# Maduino_Zero_4G_LTE_CAT4_SIM7600X-H_v1_3.net
KiCad netlist of a schematic drawn in EAGLE
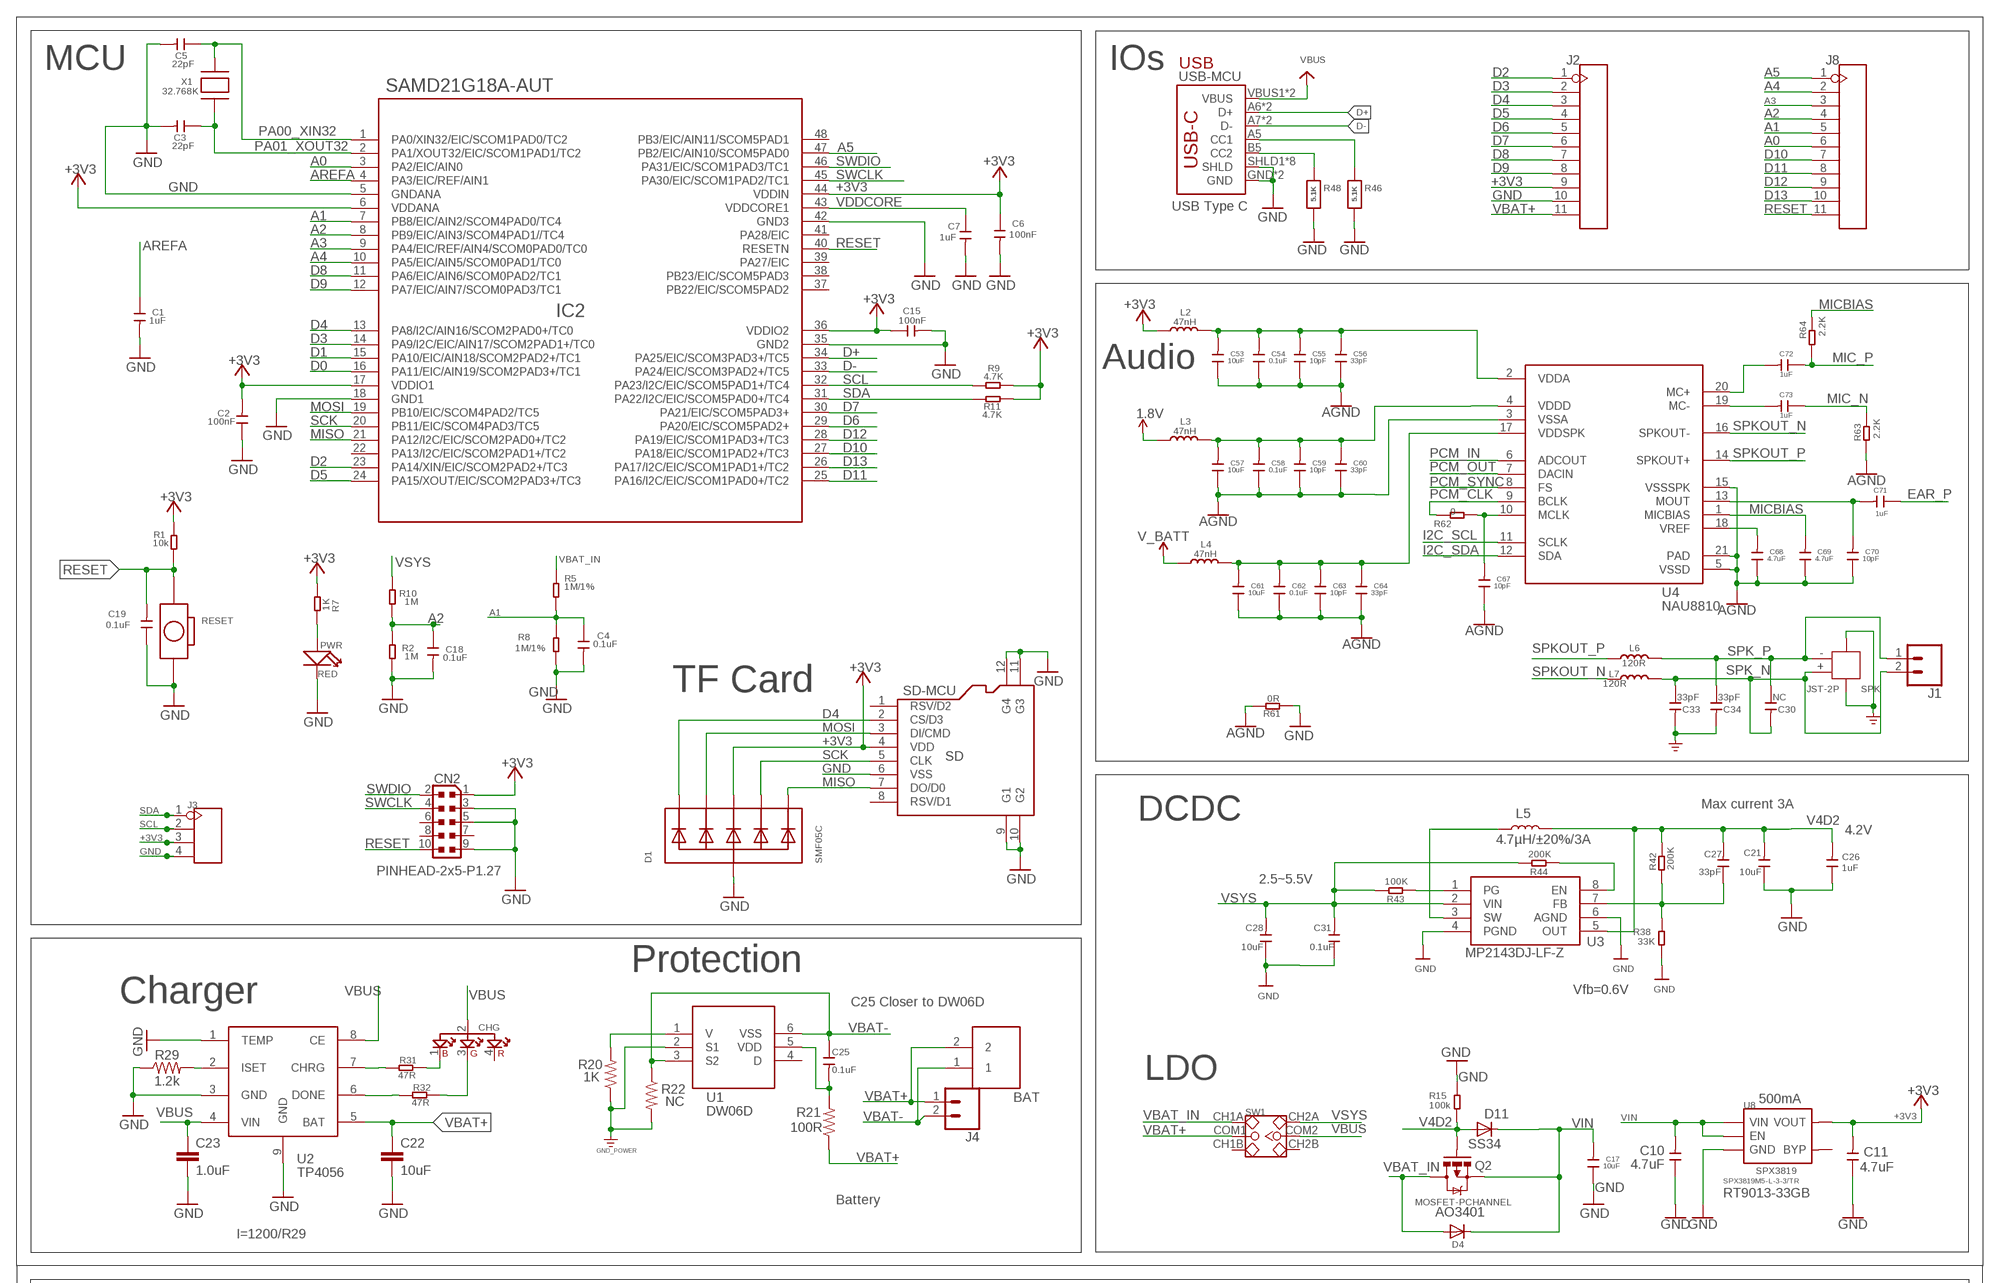
[diagram p0: schematic, sheet 1, part 1 of 2]
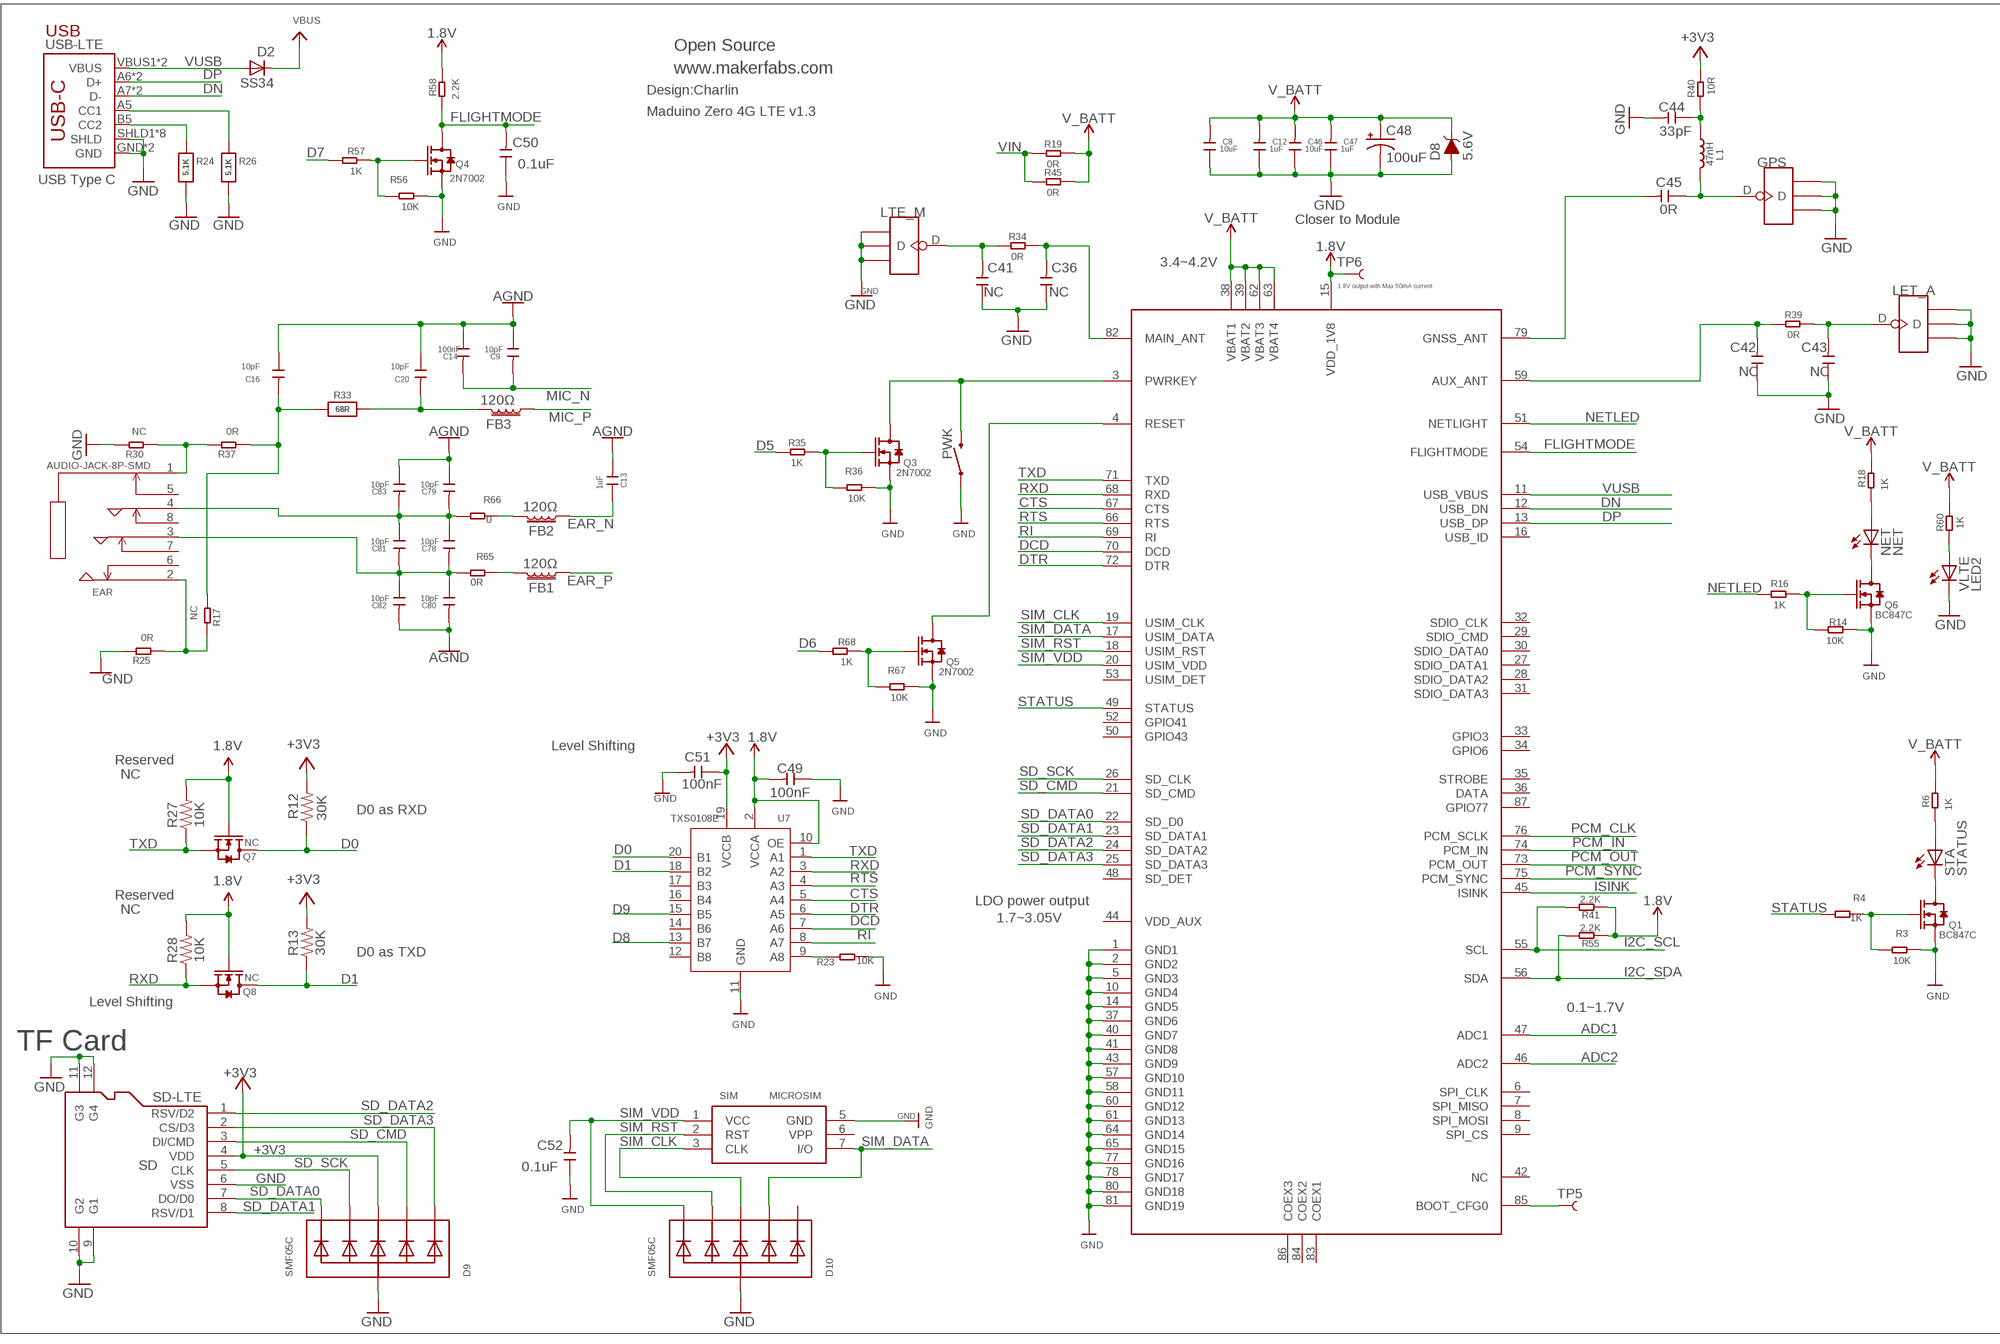
[diagram p1: schematic, sheet 1, part 2 of 2]

(export (version "E")
  (design (tool "Eeschema 10.0.6"))
  (components
    (comp (ref "BAT")
      (value "PH2.0-2P-90-DIP")
      (footprint "eagle-import:PH2.0-2P-90-DIP")
      (libsource (lib "eagle-import") (part "PH2.0-2P-90-DIP"))
    )
    (comp (ref "C1")
      (value "1uF")
      (footprint "eagle-import:0603")
      (libsource (lib "eagle-import") (part "C-0603"))
    )
    (comp (ref "C2")
      (value "100nF")
      (footprint "eagle-import:0603")
      (libsource (lib "eagle-import") (part "C-0603"))
    )
    (comp (ref "C3")
      (value "22pF")
      (footprint "eagle-import:0603")
      (libsource (lib "eagle-import") (part "C-0603"))
    )
    (comp (ref "C4")
      (value "0.1uF")
      (footprint "eagle-import:0603")
      (libsource (lib "eagle-import") (part "C-0603"))
    )
    (comp (ref "C5")
      (value "22pF")
      (footprint "eagle-import:0603")
      (libsource (lib "eagle-import") (part "C-0603"))
    )
    (comp (ref "C6")
      (value "100nF")
      (footprint "eagle-import:0603")
      (libsource (lib "eagle-import") (part "C-0603"))
    )
    (comp (ref "C7")
      (value "1uF")
      (footprint "eagle-import:0603")
      (libsource (lib "eagle-import") (part "C-0603"))
    )
    (comp (ref "C8")
      (value "10uF")
      (footprint "eagle-import:0603")
      (libsource (lib "eagle-import") (part "C-0603"))
    )
    (comp (ref "C9")
      (value "10pF")
      (footprint "eagle-import:0603")
      (libsource (lib "eagle-import") (part "C-0603"))
    )
    (comp (ref "C10")
      (value "4.7uF")
      (footprint "eagle-import:0603")
      (libsource (lib "eagle-import") (part "C-0603"))
    )
    (comp (ref "C11")
      (value "4.7uF")
      (footprint "eagle-import:0603")
      (libsource (lib "eagle-import") (part "C-0603"))
    )
    (comp (ref "C12")
      (value "1uF")
      (footprint "eagle-import:0603")
      (libsource (lib "eagle-import") (part "C-0603"))
    )
    (comp (ref "C13")
      (value "1uF")
      (footprint "eagle-import:0603")
      (libsource (lib "eagle-import") (part "C-0603"))
    )
    (comp (ref "C14")
      (value "100nF")
      (footprint "eagle-import:0603")
      (libsource (lib "eagle-import") (part "C-0603"))
    )
    (comp (ref "C15")
      (value "100nF")
      (footprint "eagle-import:0603")
      (libsource (lib "eagle-import") (part "C-0603"))
    )
    (comp (ref "C16")
      (value "10pF")
      (footprint "eagle-import:0603")
      (libsource (lib "eagle-import") (part "C-0603"))
    )
    (comp (ref "C17")
      (value "10uF")
      (footprint "eagle-import:0603")
      (libsource (lib "eagle-import") (part "C-0603"))
    )
    (comp (ref "C18")
      (value "0.1uF")
      (footprint "eagle-import:0603")
      (libsource (lib "eagle-import") (part "C-0603"))
    )
    (comp (ref "C19")
      (value "0.1uF")
      (footprint "eagle-import:0603")
      (libsource (lib "eagle-import") (part "C-0603"))
    )
    (comp (ref "C20")
      (value "10pF")
      (footprint "eagle-import:0603")
      (libsource (lib "eagle-import") (part "C-0603"))
    )
    (comp (ref "C21")
      (value "10uF")
      (footprint "eagle-import:0603")
      (libsource (lib "eagle-import") (part "C-0603"))
    )
    (comp (ref "C22")
      (value "10uF")
      (footprint "eagle-import:0603")
      (fields (field (name "PROD_ID") "CAP-00868"))
      (libsource (lib "eagle-import") (part "1.0UF-0603-16V-10%"))
    )
    (comp (ref "C23")
      (value "1.0uF")
      (footprint "eagle-import:0603")
      (libsource (lib "eagle-import") (part "1.0UF-0603-16V-10%"))
    )
    (comp (ref "C25")
      (value "0.1uF")
      (footprint "eagle-import:0603")
      (libsource (lib "eagle-import") (part "C-0603"))
    )
    (comp (ref "C26")
      (value "1uF")
      (footprint "eagle-import:0603")
      (libsource (lib "eagle-import") (part "C-0603"))
    )
    (comp (ref "C27")
      (value "33pF")
      (footprint "eagle-import:0603")
      (libsource (lib "eagle-import") (part "C-0603"))
    )
    (comp (ref "C28")
      (value "10uF")
      (footprint "eagle-import:0603")
      (libsource (lib "eagle-import") (part "C-0603"))
    )
    (comp (ref "C30")
      (value "NC")
      (footprint "eagle-import:C0603")
      (libsource (lib "eagle-import") (part "CAP-0603"))
    )
    (comp (ref "C31")
      (value "0.1uF")
      (footprint "eagle-import:0603")
      (libsource (lib "eagle-import") (part "C-0603"))
    )
    (comp (ref "C33")
      (value "33pF")
      (footprint "eagle-import:C0603")
      (libsource (lib "eagle-import") (part "CAP-0603"))
    )
    (comp (ref "C34")
      (value "33pF")
      (footprint "eagle-import:C0603")
      (libsource (lib "eagle-import") (part "CAP-0603"))
    )
    (comp (ref "C36")
      (value "NC")
      (footprint "eagle-import:0603")
      (libsource (lib "eagle-import") (part "C-0603"))
    )
    (comp (ref "C41")
      (value "NC")
      (footprint "eagle-import:0603")
      (libsource (lib "eagle-import") (part "C-0603"))
    )
    (comp (ref "C42")
      (value "NC")
      (footprint "eagle-import:0603")
      (libsource (lib "eagle-import") (part "C-0603"))
    )
    (comp (ref "C43")
      (value "NC")
      (footprint "eagle-import:0603")
      (libsource (lib "eagle-import") (part "C-0603"))
    )
    (comp (ref "C44")
      (value "33pF")
      (footprint "eagle-import:0603")
      (libsource (lib "eagle-import") (part "C-0603"))
    )
    (comp (ref "C45")
      (value "0R")
      (footprint "eagle-import:0603")
      (libsource (lib "eagle-import") (part "C-0603"))
    )
    (comp (ref "C46")
      (value "10uF")
      (footprint "eagle-import:0603")
      (libsource (lib "eagle-import") (part "C-0603"))
    )
    (comp (ref "C47")
      (value "1uF")
      (footprint "eagle-import:0603")
      (libsource (lib "eagle-import") (part "C-0603"))
    )
    (comp (ref "C48")
      (value "100uF")
      (footprint "eagle-import:EIA3528")
      (libsource (lib "eagle-import") (part "68UF-POLAR-EIA3528-10V-10%(TANT)"))
    )
    (comp (ref "C49")
      (value "100nF")
      (footprint "eagle-import:0603")
      (libsource (lib "eagle-import") (part "C-0603"))
    )
    (comp (ref "C50")
      (value "0.1uF")
      (footprint "eagle-import:0603")
      (libsource (lib "eagle-import") (part "C-0603"))
    )
    (comp (ref "C51")
      (value "100nF")
      (footprint "eagle-import:0603")
      (libsource (lib "eagle-import") (part "C-0603"))
    )
    (comp (ref "C52")
      (value "0.1uF")
      (footprint "eagle-import:0603")
      (libsource (lib "eagle-import") (part "C-0603"))
    )
    (comp (ref "C53")
      (value "10uF")
      (footprint "eagle-import:0603")
      (libsource (lib "eagle-import") (part "C-0603"))
    )
    (comp (ref "C54")
      (value "0.1uF")
      (footprint "eagle-import:0603")
      (libsource (lib "eagle-import") (part "C-0603"))
    )
    (comp (ref "C55")
      (value "10pF")
      (footprint "eagle-import:0603")
      (libsource (lib "eagle-import") (part "C-0603"))
    )
    (comp (ref "C56")
      (value "33pF")
      (footprint "eagle-import:0603")
      (libsource (lib "eagle-import") (part "C-0603"))
    )
    (comp (ref "C57")
      (value "10uF")
      (footprint "eagle-import:0603")
      (libsource (lib "eagle-import") (part "C-0603"))
    )
    (comp (ref "C58")
      (value "0.1uF")
      (footprint "eagle-import:0603")
      (libsource (lib "eagle-import") (part "C-0603"))
    )
    (comp (ref "C59")
      (value "10pF")
      (footprint "eagle-import:0603")
      (libsource (lib "eagle-import") (part "C-0603"))
    )
    (comp (ref "C60")
      (value "33pF")
      (footprint "eagle-import:0603")
      (libsource (lib "eagle-import") (part "C-0603"))
    )
    (comp (ref "C61")
      (value "10uF")
      (footprint "eagle-import:0603")
      (libsource (lib "eagle-import") (part "C-0603"))
    )
    (comp (ref "C62")
      (value "0.1uF")
      (footprint "eagle-import:0603")
      (libsource (lib "eagle-import") (part "C-0603"))
    )
    (comp (ref "C63")
      (value "10pF")
      (footprint "eagle-import:0603")
      (libsource (lib "eagle-import") (part "C-0603"))
    )
    (comp (ref "C64")
      (value "33pF")
      (footprint "eagle-import:0603")
      (libsource (lib "eagle-import") (part "C-0603"))
    )
    (comp (ref "C67")
      (value "10pF")
      (footprint "eagle-import:0603")
      (libsource (lib "eagle-import") (part "C-0603"))
    )
    (comp (ref "C68")
      (value "4.7uF")
      (footprint "eagle-import:0603")
      (libsource (lib "eagle-import") (part "C-0603"))
    )
    (comp (ref "C69")
      (value "4.7uF")
      (footprint "eagle-import:0603")
      (libsource (lib "eagle-import") (part "C-0603"))
    )
    (comp (ref "C70")
      (value "10pF")
      (footprint "eagle-import:0603")
      (libsource (lib "eagle-import") (part "C-0603"))
    )
    (comp (ref "C71")
      (value "1uF")
      (footprint "eagle-import:0603")
      (libsource (lib "eagle-import") (part "C-0603"))
    )
    (comp (ref "C72")
      (value "1uF")
      (footprint "eagle-import:0603")
      (libsource (lib "eagle-import") (part "C-0603"))
    )
    (comp (ref "C73")
      (value "1uF")
      (footprint "eagle-import:0603")
      (libsource (lib "eagle-import") (part "C-0603"))
    )
    (comp (ref "C78")
      (value "10pF")
      (footprint "eagle-import:0603")
      (libsource (lib "eagle-import") (part "C-0603"))
    )
    (comp (ref "C79")
      (value "10pF")
      (footprint "eagle-import:0603")
      (libsource (lib "eagle-import") (part "C-0603"))
    )
    (comp (ref "C80")
      (value "10pF")
      (footprint "eagle-import:0603")
      (libsource (lib "eagle-import") (part "C-0603"))
    )
    (comp (ref "C81")
      (value "10pF")
      (footprint "eagle-import:0603")
      (libsource (lib "eagle-import") (part "C-0603"))
    )
    (comp (ref "C82")
      (value "10pF")
      (footprint "eagle-import:0603")
      (libsource (lib "eagle-import") (part "C-0603"))
    )
    (comp (ref "C83")
      (value "10pF")
      (footprint "eagle-import:0603")
      (libsource (lib "eagle-import") (part "C-0603"))
    )
    (comp (ref "CHG")
      (value "E6C0606RGBC3UDA")
      (footprint "eagle-import:SMD4-160L160W")
      (libsource (lib "eagle-import") (part "E6C0606RGBC3UDA"))
    )
    (comp (ref "CN2")
      (value "PINHEAD-2x5-P1.27")
      (footprint "eagle-import:PINHEAD_2X05_127")
      (libsource (lib "eagle-import") (part "0171_PH127-205DF055G00AROUND-PADS"))
    )
    (comp (ref "D1")
      (value "SMF05C")
      (footprint "eagle-import:SOT363")
      (libsource (lib "eagle-import") (part "TVSARRAY_5LANE"))
    )
    (comp (ref "D2")
      (value "SS34")
      (footprint "eagle-import:DO-214AC")
      (libsource (lib "eagle-import") (part "DIODE-DO-214AC"))
    )
    (comp (ref "D4")
      (value "DIODESOD-323F")
      (footprint "eagle-import:SOD-323F")
      (libsource (lib "eagle-import") (part "DIODESOD-323F"))
    )
    (comp (ref "D8")
      (value "5.6V")
      (footprint "eagle-import:SOD-323")
      (libsource (lib "eagle-import") (part "DIODE-ZENER-MMSZ5232BS"))
    )
    (comp (ref "D9")
      (value "SMF05C")
      (footprint "eagle-import:SOT363")
      (libsource (lib "eagle-import") (part "TVSARRAY_5LANE"))
    )
    (comp (ref "D10")
      (value "SMF05C")
      (footprint "eagle-import:SOT363")
      (libsource (lib "eagle-import") (part "TVSARRAY_5LANE"))
    )
    (comp (ref "D11")
      (value "SS34")
      (footprint "eagle-import:DO-214AC")
      (libsource (lib "eagle-import") (part "DIODE-DO-214AC"))
    )
    (comp (ref "EAR")
      (value "AUDIO-JACK-8P-SMD")
      (footprint "eagle-import:AUDIO8P-SMD-3.5-14.5X6.1X4.0MM")
      (libsource (lib "eagle-import") (part "AUDIO-JACK-8P-SMD'PJ-393'"))
    )
    (comp (ref "FB1")
      (value "120Ω")
      (footprint "eagle-import:0603")
      (libsource (lib "eagle-import") (part "FERRITE_BEAD-0603"))
    )
    (comp (ref "FB2")
      (value "120Ω")
      (footprint "eagle-import:0603")
      (fields (field (name "PROD_ID") "NDUC-13805"))
      (libsource (lib "eagle-import") (part "FERRITE_BEAD-0603"))
    )
    (comp (ref "FB3")
      (value "120Ω")
      (footprint "eagle-import:0603")
      (fields (field (name "PROD_ID") "NDUC-13805"))
      (libsource (lib "eagle-import") (part "FERRITE_BEAD-0603"))
    )
    (comp (ref "GPS")
      (value "ANTENNA-U-FL")
      (footprint "eagle-import:4P-U-FL")
      (libsource (lib "eagle-import") (part "ANTENNA-U-FL"))
    )
    (comp (ref "IC2")
      (value "SAMD21G18A-AUT")
      (footprint "eagle-import:TQFP48-7X7")
      (libsource (lib "eagle-import") (part "ATSAMD21G18A-AUT"))
    )
    (comp (ref "J1")
      (value "CONN_02LOCK")
      (footprint "eagle-import:1X02_LOCK")
      (libsource (lib "eagle-import") (part "CONN_02LOCK"))
    )
    (comp (ref "J2")
      (value "HEADER-11P-2.54")
      (footprint "eagle-import:11P-2.54")
      (libsource (lib "eagle-import") (part "HEADER-11P-2.54"))
    )
    (comp (ref "J3")
      (value "HEADER-4P-60/35MILROUND")
      (footprint "eagle-import:4P-65_35ROUND")
      (libsource (lib "eagle-import") (part "HEADER-4P-60/35MILROUND"))
    )
    (comp (ref "J4")
      (value "CONN_02LOCK")
      (footprint "eagle-import:1X02_LOCK")
      (libsource (lib "eagle-import") (part "CONN_02LOCK"))
    )
    (comp (ref "J8")
      (value "HEADER-11P-2.54")
      (footprint "eagle-import:11P-2.54")
      (libsource (lib "eagle-import") (part "HEADER-11P-2.54"))
    )
    (comp (ref "L1")
      (value "47nH")
      (footprint "eagle-import:L0603")
      (libsource (lib "eagle-import") (part "L'0603'"))
    )
    (comp (ref "L2")
      (value "47nH")
      (footprint "eagle-import:L0603")
      (libsource (lib "eagle-import") (part "L'0603'"))
    )
    (comp (ref "L3")
      (value "47nH")
      (footprint "eagle-import:L0603")
      (libsource (lib "eagle-import") (part "L'0603'"))
    )
    (comp (ref "L4")
      (value "47nH")
      (footprint "eagle-import:L0603")
      (libsource (lib "eagle-import") (part "L'0603'"))
    )
    (comp (ref "L5")
      (value "4.7µH/±20%/3A")
      (footprint "eagle-import:SRN6045")
      (libsource (lib "eagle-import") (part "INDUCTOR-SRN6045-33UH"))
    )
    (comp (ref "L6")
      (value "120R")
      (footprint "eagle-import:L0603")
      (libsource (lib "eagle-import") (part "INDUCTOR/FERRITE-BEAD'0603'"))
    )
    (comp (ref "L7")
      (value "120R")
      (footprint "eagle-import:L0603")
      (libsource (lib "eagle-import") (part "INDUCTOR/FERRITE-BEAD'0603'"))
    )
    (comp (ref "LET_A")
      (value "ANTENNA-U-FL")
      (footprint "eagle-import:4P-U-FL")
      (libsource (lib "eagle-import") (part "ANTENNA-U-FL"))
    )
    (comp (ref "LTE_M")
      (value "ANTENNA-U-FL")
      (footprint "eagle-import:4P-U-FL")
      (libsource (lib "eagle-import") (part "ANTENNA-U-FL"))
    )
    (comp (ref "NET")
      (value "NET")
      (footprint "eagle-import:CHIP-LED0805")
      (libsource (lib "eagle-import") (part "LEDCHIP-LED0805"))
    )
    (comp (ref "PWK")
      (value "MOMENTARY-SWITCH-SPST-SMD-6.0X3.5MM")
      (footprint "eagle-import:TACTILE_SWITCH_SMD_6.0X3.5MM")
      (libsource (lib "eagle-import") (part "MOMENTARY-SWITCH-SPST-SMD-6.0X3.5MM"))
    )
    (comp (ref "PWR")
      (value "RED")
      (footprint "eagle-import:LED-0603")
      (libsource (lib "eagle-import") (part "LED'0603'"))
    )
    (comp (ref "Q1")
      (value "BC847C")
      (footprint "eagle-import:SOT23")
      (libsource (lib "eagle-import") (part "MOSFET-N'SOT23'"))
    )
    (comp (ref "Q2")
      (value "MOSFET-PCHANNEL")
      (footprint "eagle-import:SOT23-3")
      (libsource (lib "eagle-import") (part "MOSFET-PCHANNEL"))
    )
    (comp (ref "Q3")
      (value "2N7002")
      (footprint "eagle-import:SOT23")
      (libsource (lib "eagle-import") (part "MOSFET-N'SOT23'"))
    )
    (comp (ref "Q4")
      (value "2N7002")
      (footprint "eagle-import:SOT23")
      (libsource (lib "eagle-import") (part "MOSFET-N'SOT23'"))
    )
    (comp (ref "Q5")
      (value "2N7002")
      (footprint "eagle-import:SOT23")
      (libsource (lib "eagle-import") (part "MOSFET-N'SOT23'"))
    )
    (comp (ref "Q6")
      (value "BC847C")
      (footprint "eagle-import:SOT23")
      (libsource (lib "eagle-import") (part "MOSFET-N'SOT23'"))
    )
    (comp (ref "Q7")
      (value "NC")
      (footprint "eagle-import:SOT23")
      (libsource (lib "eagle-import") (part "MOSFET-N'SOT23'"))
    )
    (comp (ref "Q8")
      (value "NC")
      (footprint "eagle-import:SOT23")
      (libsource (lib "eagle-import") (part "MOSFET-N'SOT23'"))
    )
    (comp (ref "R1")
      (value "10k")
      (footprint "eagle-import:R0603")
      (libsource (lib "eagle-import") (part "R-0603"))
    )
    (comp (ref "R2")
      (value "1M")
      (footprint "eagle-import:R0603")
      (libsource (lib "eagle-import") (part "R-0603"))
    )
    (comp (ref "R3")
      (value "10K")
      (footprint "eagle-import:R0603")
      (libsource (lib "eagle-import") (part "R-0603"))
    )
    (comp (ref "R4")
      (value "1K")
      (footprint "eagle-import:R0603")
      (libsource (lib "eagle-import") (part "R-0603"))
    )
    (comp (ref "R5")
      (value "1M/1%")
      (footprint "eagle-import:R0603")
      (libsource (lib "eagle-import") (part "R-0603"))
    )
    (comp (ref "R6")
      (value "1K")
      (footprint "eagle-import:R0603")
      (libsource (lib "eagle-import") (part "R-0603"))
    )
    (comp (ref "R7")
      (value "1K")
      (footprint "eagle-import:R0603")
      (libsource (lib "eagle-import") (part "R-0603"))
    )
    (comp (ref "R8")
      (value "1M/1%")
      (footprint "eagle-import:R0603")
      (libsource (lib "eagle-import") (part "R-0603"))
    )
    (comp (ref "R9")
      (value "4.7K")
      (footprint "eagle-import:R0603")
      (libsource (lib "eagle-import") (part "R-0603"))
    )
    (comp (ref "R10")
      (value "1M")
      (footprint "eagle-import:R0603")
      (libsource (lib "eagle-import") (part "R-0603"))
    )
    (comp (ref "R11")
      (value "4.7K")
      (footprint "eagle-import:R0603")
      (libsource (lib "eagle-import") (part "R-0603"))
    )
    (comp (ref "R12")
      (value "30K")
      (footprint "eagle-import:0603")
      (fields (field (name "PROD_ID") "RES-10809"))
      (libsource (lib "eagle-import") (part "300KOHM-0603-1/10W-1%"))
    )
    (comp (ref "R13")
      (value "30K")
      (footprint "eagle-import:0603")
      (fields (field (name "PROD_ID") "RES-10809"))
      (libsource (lib "eagle-import") (part "300KOHM-0603-1/10W-1%"))
    )
    (comp (ref "R14")
      (value "10K")
      (footprint "eagle-import:R0603")
      (libsource (lib "eagle-import") (part "R-0603"))
    )
    (comp (ref "R15")
      (value "100k")
      (footprint "eagle-import:R0603")
      (libsource (lib "eagle-import") (part "R-0603"))
    )
    (comp (ref "R16")
      (value "1K")
      (footprint "eagle-import:R0603")
      (libsource (lib "eagle-import") (part "R-0603"))
    )
    (comp (ref "R17")
      (value "NC")
      (footprint "eagle-import:R0603")
      (libsource (lib "eagle-import") (part "R-0603"))
    )
    (comp (ref "R18")
      (value "1K")
      (footprint "eagle-import:R0603")
      (libsource (lib "eagle-import") (part "R-0603"))
    )
    (comp (ref "R19")
      (value "0R")
      (footprint "eagle-import:R0603")
      (libsource (lib "eagle-import") (part "R-0603"))
    )
    (comp (ref "R20")
      (value "1K")
      (footprint "eagle-import:0603")
      (fields (field (name "PROD_ID") "RES-00824"))
      (libsource (lib "eagle-import") (part "10KOHM-0603-1/10W-1%"))
    )
    (comp (ref "R21")
      (value "100R")
      (footprint "eagle-import:0603")
      (fields (field (name "PROD_ID") "RES-00824"))
      (libsource (lib "eagle-import") (part "10KOHM-0603-1/10W-1%"))
    )
    (comp (ref "R22")
      (value "NC")
      (footprint "eagle-import:0603")
      (fields (field (name "PROD_ID") "RES-00824"))
      (libsource (lib "eagle-import") (part "10KOHM-0603-1/10W-1%"))
    )
    (comp (ref "R23")
      (value "10K")
      (footprint "eagle-import:R0603")
      (libsource (lib "eagle-import") (part "R-0603"))
    )
    (comp (ref "R24")
      (value "5.1K")
      (footprint "eagle-import:0603-NO")
      (libsource (lib "eagle-import") (part "RESISTOR_0603_NOOUT"))
    )
    (comp (ref "R25")
      (value "0R")
      (footprint "eagle-import:R0603")
      (libsource (lib "eagle-import") (part "R-0603"))
    )
    (comp (ref "R26")
      (value "5.1K")
      (footprint "eagle-import:0603-NO")
      (libsource (lib "eagle-import") (part "RESISTOR_0603_NOOUT"))
    )
    (comp (ref "R27")
      (value "10K")
      (footprint "eagle-import:0603")
      (fields (field (name "PROD_ID") "RES-10809"))
      (libsource (lib "eagle-import") (part "300KOHM-0603-1/10W-1%"))
    )
    (comp (ref "R28")
      (value "10K")
      (footprint "eagle-import:0603")
      (fields (field (name "PROD_ID") "RES-10809"))
      (libsource (lib "eagle-import") (part "300KOHM-0603-1/10W-1%"))
    )
    (comp (ref "R29")
      (value "1.2k")
      (footprint "eagle-import:0603")
      (libsource (lib "eagle-import") (part "2.49KOHM-0603-1/10W-1%"))
    )
    (comp (ref "R30")
      (value "NC")
      (footprint "eagle-import:R0603")
      (libsource (lib "eagle-import") (part "R-0603"))
    )
    (comp (ref "R31")
      (value "47R")
      (footprint "eagle-import:R0603")
      (libsource (lib "eagle-import") (part "R-0603"))
    )
    (comp (ref "R32")
      (value "47R")
      (footprint "eagle-import:R0603")
      (libsource (lib "eagle-import") (part "R-0603"))
    )
    (comp (ref "R33")
      (value "68R")
      (footprint "eagle-import:0603-NO")
      (libsource (lib "eagle-import") (part "RESISTOR_0603_NOOUT"))
    )
    (comp (ref "R34")
      (value "0R")
      (footprint "eagle-import:R0603")
      (libsource (lib "eagle-import") (part "R-0603"))
    )
    (comp (ref "R35")
      (value "1K")
      (footprint "eagle-import:R0603")
      (libsource (lib "eagle-import") (part "R-0603"))
    )
    (comp (ref "R36")
      (value "10K")
      (footprint "eagle-import:R0603")
      (libsource (lib "eagle-import") (part "R-0603"))
    )
    (comp (ref "R37")
      (value "0R")
      (footprint "eagle-import:R0603")
      (libsource (lib "eagle-import") (part "R-0603"))
    )
    (comp (ref "R38")
      (value "33K")
      (footprint "eagle-import:R0603")
      (libsource (lib "eagle-import") (part "R-0603"))
    )
    (comp (ref "R39")
      (value "0R")
      (footprint "eagle-import:R0603")
      (libsource (lib "eagle-import") (part "R-0603"))
    )
    (comp (ref "R40")
      (value "10R")
      (footprint "eagle-import:R0603")
      (libsource (lib "eagle-import") (part "R-0603"))
    )
    (comp (ref "R41")
      (value "2.2K")
      (footprint "eagle-import:R0603")
      (libsource (lib "eagle-import") (part "R-0603"))
    )
    (comp (ref "R42")
      (value "200K")
      (footprint "eagle-import:R0603")
      (libsource (lib "eagle-import") (part "R-0603"))
    )
    (comp (ref "R43")
      (value "100K")
      (footprint "eagle-import:R0603")
      (libsource (lib "eagle-import") (part "R-0603"))
    )
    (comp (ref "R44")
      (value "200K")
      (footprint "eagle-import:R0603")
      (libsource (lib "eagle-import") (part "R-0603"))
    )
    (comp (ref "R45")
      (value "0R")
      (footprint "eagle-import:R0603")
      (libsource (lib "eagle-import") (part "R-0603"))
    )
    (comp (ref "R46")
      (value "5.1K")
      (footprint "eagle-import:0603-NO")
      (libsource (lib "eagle-import") (part "RESISTOR_0603_NOOUT"))
    )
    (comp (ref "R48")
      (value "5.1K")
      (footprint "eagle-import:0603-NO")
      (libsource (lib "eagle-import") (part "RESISTOR_0603_NOOUT"))
    )
    (comp (ref "R55")
      (value "2.2K")
      (footprint "eagle-import:R0603")
      (libsource (lib "eagle-import") (part "R-0603"))
    )
    (comp (ref "R56")
      (value "10K")
      (footprint "eagle-import:R0603")
      (libsource (lib "eagle-import") (part "R-0603"))
    )
    (comp (ref "R57")
      (value "1K")
      (footprint "eagle-import:R0603")
      (libsource (lib "eagle-import") (part "R-0603"))
    )
    (comp (ref "R58")
      (value "2.2K")
      (footprint "eagle-import:R0603")
      (libsource (lib "eagle-import") (part "R-0603"))
    )
    (comp (ref "R60")
      (value "1K")
      (footprint "eagle-import:R0603")
      (libsource (lib "eagle-import") (part "R-0603"))
    )
    (comp (ref "R61")
      (value "0R")
      (footprint "eagle-import:R0603")
      (libsource (lib "eagle-import") (part "R-0603"))
    )
    (comp (ref "R62")
      (value "0")
      (footprint "eagle-import:R0603")
      (libsource (lib "eagle-import") (part "R-0603"))
    )
    (comp (ref "R63")
      (value "2.2K")
      (footprint "eagle-import:R0603")
      (libsource (lib "eagle-import") (part "R-0603"))
    )
    (comp (ref "R64")
      (value "2.2K")
      (footprint "eagle-import:R0603")
      (libsource (lib "eagle-import") (part "R-0603"))
    )
    (comp (ref "R65")
      (value "0R")
      (footprint "eagle-import:R0603")
      (libsource (lib "eagle-import") (part "R-0603"))
    )
    (comp (ref "R66")
      (value "0")
      (footprint "eagle-import:R0603")
      (libsource (lib "eagle-import") (part "R-0603"))
    )
    (comp (ref "R67")
      (value "10K")
      (footprint "eagle-import:R0603")
      (libsource (lib "eagle-import") (part "R-0603"))
    )
    (comp (ref "R68")
      (value "1K")
      (footprint "eagle-import:R0603")
      (libsource (lib "eagle-import") (part "R-0603"))
    )
    (comp (ref "RESET")
      (value "BOTTON-2P-90D")
      (footprint "eagle-import:2P-7.62X3.56-90D")
      (libsource (lib "eagle-import") (part "BOTTON-2P-90D"))
    )
    (comp (ref "SD-LTE")
      (value "SD")
      (footprint "eagle-import:8P-SMD")
      (libsource (lib "eagle-import") (part "HOLDER-MICROSD-8P"))
    )
    (comp (ref "SD-MCU")
      (value "SD")
      (footprint "eagle-import:8P-SMD")
      (libsource (lib "eagle-import") (part "HOLDER-MICROSD-8P"))
    )
    (comp (ref "SIM")
      (value "MICROSIM")
      (footprint "eagle-import:MICROSIM")
      (libsource (lib "eagle-import") (part "MICROSIM"))
    )
    (comp (ref "SPK")
      (value "JST-2P")
      (footprint "eagle-import:HW2-SMD-2.0-90D")
      (libsource (lib "eagle-import") (part "JST-2P-SMD'2.0'"))
    )
    (comp (ref "STA")
      (value "STATUS")
      (footprint "eagle-import:CHIP-LED0805")
      (libsource (lib "eagle-import") (part "LEDCHIP-LED0805"))
    )
    (comp (ref "SW1")
      (value "SWITCH-2CH-6P")
      (footprint "eagle-import:6P-2CH-2.54-7.6X3.0")
      (libsource (lib "eagle-import") (part "SWITCH-2CH-6P"))
    )
    (comp (ref "TP5")
      (value "TEST-POINT3")
      (footprint "eagle-import:PAD.03X.03")
      (libsource (lib "eagle-import") (part "TEST-POINT3"))
    )
    (comp (ref "TP6")
      (value "TEST-POINT3")
      (footprint "eagle-import:PAD.03X.03")
      (libsource (lib "eagle-import") (part "TEST-POINT3"))
    )
    (comp (ref "U1")
      (value "DW06D")
      (footprint "eagle-import:SOT-23-6")
      (libsource (lib "eagle-import") (part "DW06D"))
    )
    (comp (ref "U2")
      (value "TP4056")
      (footprint "eagle-import:SOP8-1.27P")
      (libsource (lib "eagle-import") (part "TP4056"))
    )
    (comp (ref "U3")
      (value "MP2143DJ-LF-Z")
      (footprint "eagle-import:TSOT23-8")
      (libsource (lib "eagle-import") (part "MP2143DJ-LF-Z"))
    )
    (comp (ref "U4")
      (value "NAU8810")
      (footprint "eagle-import:QFN21-50P-400L400W")
      (libsource (lib "eagle-import") (part "NAU8810"))
    )
    (comp (ref "U6")
      (value "SIM7600")
      (footprint "eagle-import:SMD87-100P-3000L300W")
      (libsource (lib "eagle-import") (part "SIM7600"))
    )
    (comp (ref "U7")
      (value "TXS0108E")
      (footprint "eagle-import:TSSOP20-0.65-6.5X4.4MM")
      (libsource (lib "eagle-import") (part "LOGIC-TXS0108EPWR"))
    )
    (comp (ref "U8")
      (value "SPX3819")
      (footprint "eagle-import:SOT23-5")
      (libsource (lib "eagle-import") (part "SPX3819"))
    )
    (comp (ref "USB-LTE")
      (value "USB_C5")
      (footprint "eagle-import:USB-C-16P-5")
      (libsource (lib "eagle-import") (part "USB_C5"))
    )
    (comp (ref "USB-MCU")
      (value "USB_C5")
      (footprint "eagle-import:USB-C-16P-5")
      (libsource (lib "eagle-import") (part "USB_C5"))
    )
    (comp (ref "VLTE")
      (value "LED2")
      (footprint "eagle-import:CHIP-LED0805")
      (libsource (lib "eagle-import") (part "LEDCHIP-LED0805"))
    )
    (comp (ref "X1")
      (value "32.768K")
      (footprint "eagle-import:XTAL3215")
      (libsource (lib "eagle-import") (part "XTAL-3.2X1.5"))
    )
  )
  (nets
    (net (code "1") (name "+3V3") (class "Default")
      (node (ref "C11") (pin "2") (pinfunction "2_2") (pintype "passive"))
      (node (ref "C15") (pin "1") (pinfunction "1_1") (pintype "passive"))
      (node (ref "C2") (pin "2") (pinfunction "2_2") (pintype "passive"))
      (node (ref "C51") (pin "1") (pinfunction "1_1") (pintype "passive"))
      (node (ref "C6") (pin "1") (pinfunction "1_1") (pintype "passive"))
      (node (ref "CN2") (pin "1") (pinfunction "1_1") (pintype "passive"))
      (node (ref "D1") (pin "4") (pinfunction "C3_4") (pintype "passive"))
      (node (ref "D9") (pin "4") (pinfunction "C3_4") (pintype "passive"))
      (node (ref "IC2") (pin "17") (pinfunction "VDDIO1_17") (pintype "power_in"))
      (node (ref "IC2") (pin "36") (pinfunction "VDDIO2_36") (pintype "power_in"))
      (node (ref "IC2") (pin "44") (pinfunction "VDDIN_44") (pintype "power_in"))
      (node (ref "IC2") (pin "6") (pinfunction "VDDANA_6") (pintype "power_in"))
      (node (ref "J2") (pin "9") (pinfunction "9_9") (pintype "bidirectional"))
      (node (ref "J3") (pin "3") (pinfunction "P$3_3") (pintype "bidirectional"))
      (node (ref "L2") (pin "1") (pinfunction "1_1") (pintype "passive"))
      (node (ref "R1") (pin "2") (pinfunction "2_2") (pintype "passive"))
      (node (ref "R11") (pin "2") (pinfunction "2_2") (pintype "passive"))
      (node (ref "R12") (pin "2") (pinfunction "2_2") (pintype "passive"))
      (node (ref "R13") (pin "2") (pinfunction "2_2") (pintype "passive"))
      (node (ref "R40") (pin "2") (pinfunction "2_2") (pintype "passive"))
      (node (ref "R7") (pin "1") (pinfunction "1_1") (pintype "passive"))
      (node (ref "R9") (pin "2") (pinfunction "2_2") (pintype "passive"))
      (node (ref "SD-LTE") (pin "4") (pinfunction "VDD_4") (pintype "bidirectional"))
      (node (ref "SD-MCU") (pin "4") (pinfunction "VDD_4") (pintype "bidirectional"))
      (node (ref "U7") (pin "19") (pinfunction "VCCB_19") (pintype "bidirectional"))
      (node (ref "U8") (pin "5") (pinfunction "VOUT_5") (pintype "bidirectional"))
    )
    (net (code "2") (name "/A0") (class "Default")
      (node (ref "IC2") (pin "3") (pinfunction "PA2/EIC/AIN0_3") (pintype "bidirectional"))
      (node (ref "J8") (pin "6") (pinfunction "6_6") (pintype "bidirectional"))
    )
    (net (code "3") (name "/A1") (class "Default")
      (node (ref "C4") (pin "1") (pinfunction "1_1") (pintype "passive"))
      (node (ref "IC2") (pin "7") (pinfunction "PB8/EIC/AIN2/SCOM4PAD0/TC4_7") (pintype "bidirectional"))
      (node (ref "J8") (pin "5") (pinfunction "5_5") (pintype "bidirectional"))
      (node (ref "R5") (pin "1") (pinfunction "1_1") (pintype "passive"))
      (node (ref "R8") (pin "2") (pinfunction "2_2") (pintype "passive"))
    )
    (net (code "4") (name "/A2") (class "Default")
      (node (ref "C18") (pin "1") (pinfunction "1_1") (pintype "passive"))
      (node (ref "IC2") (pin "8") (pinfunction "PB9/EIC/AIN3/SCOM4PAD1//TC4_8") (pintype "bidirectional"))
      (node (ref "J8") (pin "4") (pinfunction "4_4") (pintype "bidirectional"))
      (node (ref "R10") (pin "1") (pinfunction "1_1") (pintype "passive"))
      (node (ref "R2") (pin "2") (pinfunction "2_2") (pintype "passive"))
    )
    (net (code "5") (name "/A3") (class "Default")
      (node (ref "IC2") (pin "9") (pinfunction "PA4/EIC/REF/AIN4/SCOM0PAD0/TC0_9") (pintype "bidirectional"))
      (node (ref "J8") (pin "3") (pinfunction "3_3") (pintype "bidirectional"))
    )
    (net (code "6") (name "/A4") (class "Default")
      (node (ref "IC2") (pin "10") (pinfunction "PA5/EIC/AIN5/SCOM0PAD1/TC0_10") (pintype "bidirectional"))
      (node (ref "J8") (pin "2") (pinfunction "2_2") (pintype "bidirectional"))
    )
    (net (code "7") (name "/A5") (class "Default")
      (node (ref "IC2") (pin "47") (pinfunction "PB2/EIC/AIN10/SCOM5PAD0_47") (pintype "bidirectional"))
      (node (ref "J8") (pin "1") (pinfunction "1_1") (pintype "bidirectional"))
    )
    (net (code "8") (name "/ADC1") (class "Default")
      (node (ref "U6") (pin "47") (pinfunction "ADC1_47") (pintype "bidirectional"))
    )
    (net (code "9") (name "/ADC2") (class "Default")
      (node (ref "U6") (pin "46") (pinfunction "ADC2_46") (pintype "bidirectional"))
    )
    (net (code "10") (name "/AREFA") (class "Default")
      (node (ref "C1") (pin "1") (pinfunction "1_1") (pintype "passive"))
      (node (ref "IC2") (pin "4") (pinfunction "PA3/EIC/REF/AIN1_4") (pintype "bidirectional"))
    )
    (net (code "11") (name "/CTS") (class "Default")
      (node (ref "U6") (pin "67") (pinfunction "CTS_67") (pintype "bidirectional"))
      (node (ref "U7") (pin "5") (pinfunction "A4_5") (pintype "bidirectional"))
    )
    (net (code "12") (name "/D0") (class "Default")
      (node (ref "IC2") (pin "16") (pinfunction "PA11/EIC/AIN19/SCOM2PAD3+/TC1_16") (pintype "bidirectional"))
      (node (ref "Q7") (pin "3") (pinfunction "D_3") (pintype "passive"))
      (node (ref "R12") (pin "1") (pinfunction "1_1") (pintype "passive"))
      (node (ref "U7") (pin "20") (pinfunction "B1_20") (pintype "bidirectional"))
    )
    (net (code "13") (name "/D1") (class "Default")
      (node (ref "IC2") (pin "15") (pinfunction "PA10/EIC/AIN18/SCOM2PAD2+/TC1_15") (pintype "bidirectional"))
      (node (ref "Q8") (pin "3") (pinfunction "D_3") (pintype "passive"))
      (node (ref "R13") (pin "1") (pinfunction "1_1") (pintype "passive"))
      (node (ref "U7") (pin "18") (pinfunction "B2_18") (pintype "bidirectional"))
    )
    (net (code "14") (name "/D2") (class "Default")
      (node (ref "IC2") (pin "23") (pinfunction "PA14/XIN/EIC/SCOM2PAD2+/TC3_23") (pintype "bidirectional"))
      (node (ref "J2") (pin "1") (pinfunction "1_1") (pintype "bidirectional"))
    )
    (net (code "15") (name "/D3") (class "Default")
      (node (ref "IC2") (pin "14") (pinfunction "PA9/I2C/EIC/AIN17/SCOM2PAD1+/TC0_14") (pintype "bidirectional"))
      (node (ref "J2") (pin "2") (pinfunction "2_2") (pintype "bidirectional"))
    )
    (net (code "16") (name "/D4") (class "Default")
      (node (ref "D1") (pin "1") (pinfunction "C1_1") (pintype "passive"))
      (node (ref "IC2") (pin "13") (pinfunction "PA8/I2C/AIN16/SCOM2PAD0+/TC0_13") (pintype "bidirectional"))
      (node (ref "J2") (pin "3") (pinfunction "3_3") (pintype "bidirectional"))
      (node (ref "SD-MCU") (pin "2") (pinfunction "CS/D3_2") (pintype "bidirectional"))
    )
    (net (code "17") (name "/D5") (class "Default")
      (node (ref "IC2") (pin "24") (pinfunction "PA15/XOUT/EIC/SCOM2PAD3+/TC3_24") (pintype "bidirectional"))
      (node (ref "J2") (pin "4") (pinfunction "4_4") (pintype "bidirectional"))
      (node (ref "R35") (pin "2") (pinfunction "2_2") (pintype "passive"))
    )
    (net (code "18") (name "/D6") (class "Default")
      (node (ref "IC2") (pin "29") (pinfunction "PA20/EIC/SCOM5PAD2+_29") (pintype "bidirectional"))
      (node (ref "J2") (pin "5") (pinfunction "5_5") (pintype "bidirectional"))
      (node (ref "R68") (pin "2") (pinfunction "2_2") (pintype "passive"))
    )
    (net (code "19") (name "/D7") (class "Default")
      (node (ref "IC2") (pin "30") (pinfunction "PA21/EIC/SCOM5PAD3+_30") (pintype "bidirectional"))
      (node (ref "J2") (pin "6") (pinfunction "6_6") (pintype "bidirectional"))
      (node (ref "R57") (pin "2") (pinfunction "2_2") (pintype "passive"))
    )
    (net (code "20") (name "/D8") (class "Default")
      (node (ref "IC2") (pin "11") (pinfunction "PA6/EIC/AIN6/SCOM0PAD2/TC1_11") (pintype "bidirectional"))
      (node (ref "J2") (pin "7") (pinfunction "7_7") (pintype "bidirectional"))
      (node (ref "U7") (pin "13") (pinfunction "B7_13") (pintype "bidirectional"))
    )
    (net (code "21") (name "/D9") (class "Default")
      (node (ref "IC2") (pin "12") (pinfunction "PA7/EIC/AIN7/SCOM0PAD3/TC1_12") (pintype "bidirectional"))
      (node (ref "J2") (pin "8") (pinfunction "8_8") (pintype "bidirectional"))
      (node (ref "U7") (pin "15") (pinfunction "B5_15") (pintype "bidirectional"))
    )
    (net (code "22") (name "/D10") (class "Default")
      (node (ref "IC2") (pin "27") (pinfunction "PA18/EIC/SCOM1PAD2+/TC3_27") (pintype "bidirectional"))
      (node (ref "J8") (pin "7") (pinfunction "7_7") (pintype "bidirectional"))
    )
    (net (code "23") (name "/D11") (class "Default")
      (node (ref "IC2") (pin "25") (pinfunction "PA16/I2C/EIC/SCOM1PAD0+/TC2_25") (pintype "bidirectional"))
      (node (ref "J8") (pin "8") (pinfunction "8_8") (pintype "bidirectional"))
    )
    (net (code "24") (name "/D12") (class "Default")
      (node (ref "IC2") (pin "28") (pinfunction "PA19/EIC/SCOM1PAD3+/TC3_28") (pintype "bidirectional"))
      (node (ref "J8") (pin "9") (pinfunction "9_9") (pintype "bidirectional"))
    )
    (net (code "25") (name "/D13") (class "Default")
      (node (ref "IC2") (pin "26") (pinfunction "PA17/I2C/EIC/SCOM1PAD1+/TC2_26") (pintype "bidirectional"))
      (node (ref "J8") (pin "10") (pinfunction "10_10") (pintype "bidirectional"))
    )
    (net (code "26") (name "/DCD") (class "Default")
      (node (ref "U6") (pin "70") (pinfunction "DCD_70") (pintype "bidirectional"))
      (node (ref "U7") (pin "7") (pinfunction "A6_7") (pintype "bidirectional"))
    )
    (net (code "27") (name "/DN") (class "Default")
      (node (ref "U6") (pin "12") (pinfunction "USB_DN_12") (pintype "bidirectional"))
      (node (ref "USB-LTE") (pin "A7") (pinfunction "D-_A7") (pintype "bidirectional"))
      (node (ref "USB-LTE") (pin "B7") (pinfunction "D-_B7") (pintype "bidirectional"))
    )
    (net (code "28") (name "/DP") (class "Default")
      (node (ref "U6") (pin "13") (pinfunction "USB_DP_13") (pintype "bidirectional"))
      (node (ref "USB-LTE") (pin "A6") (pinfunction "D+_A6") (pintype "bidirectional"))
      (node (ref "USB-LTE") (pin "B6") (pinfunction "D+_B6") (pintype "bidirectional"))
    )
    (net (code "29") (name "/DTR") (class "Default")
      (node (ref "U6") (pin "72") (pinfunction "DTR_72") (pintype "bidirectional"))
      (node (ref "U7") (pin "6") (pinfunction "A5_6") (pintype "bidirectional"))
    )
    (net (code "30") (name "/EAR_N") (class "Default")
      (node (ref "C13") (pin "1") (pinfunction "1_1") (pintype "passive"))
      (node (ref "FB2") (pin "1") (pinfunction "1_1") (pintype "passive"))
    )
    (net (code "31") (name "/EAR_P") (class "Default")
      (node (ref "C71") (pin "1") (pinfunction "1_1") (pintype "passive"))
      (node (ref "FB1") (pin "1") (pinfunction "1_1") (pintype "passive"))
    )
    (net (code "32") (name "/FLIGHTMODE") (class "Default")
      (node (ref "C50") (pin "2") (pinfunction "2_2") (pintype "passive"))
      (node (ref "Q4") (pin "3") (pinfunction "D_3") (pintype "passive"))
      (node (ref "R58") (pin "1") (pinfunction "1_1") (pintype "passive"))
      (node (ref "U6") (pin "54") (pinfunction "FLIGHTMODE_54") (pintype "bidirectional"))
    )
    (net (code "33") (name "/I2C_SCL") (class "Default")
      (node (ref "R41") (pin "2") (pinfunction "2_2") (pintype "passive"))
      (node (ref "U4") (pin "11") (pinfunction "SCLK_11") (pintype "bidirectional"))
      (node (ref "U6") (pin "55") (pinfunction "SCL_55") (pintype "bidirectional"))
    )
    (net (code "34") (name "/I2C_SDA") (class "Default")
      (node (ref "R55") (pin "2") (pinfunction "2_2") (pintype "passive"))
      (node (ref "U4") (pin "12") (pinfunction "SDA_12") (pintype "bidirectional"))
      (node (ref "U6") (pin "56") (pinfunction "SDA_56") (pintype "bidirectional"))
    )
    (net (code "35") (name "/ISINK") (class "Default")
      (node (ref "U6") (pin "45") (pinfunction "ISINK_45") (pintype "bidirectional"))
    )
    (net (code "36") (name "/MICBIAS") (class "Default")
      (node (ref "C69") (pin "2") (pinfunction "2_2") (pintype "passive"))
      (node (ref "R64") (pin "2") (pinfunction "2_2") (pintype "passive"))
      (node (ref "U4") (pin "1") (pinfunction "MICBIAS_1") (pintype "bidirectional"))
    )
    (net (code "37") (name "/MIC_N") (class "Default")
      (node (ref "C14") (pin "2") (pinfunction "2_2") (pintype "passive"))
      (node (ref "C73") (pin "1") (pinfunction "1_1") (pintype "passive"))
      (node (ref "C9") (pin "2") (pinfunction "2_2") (pintype "passive"))
      (node (ref "R63") (pin "2") (pinfunction "2_2") (pintype "passive"))
    )
    (net (code "38") (name "/MIC_P") (class "Default")
      (node (ref "C72") (pin "1") (pinfunction "1_1") (pintype "passive"))
      (node (ref "FB3") (pin "1") (pinfunction "1_1") (pintype "passive"))
      (node (ref "R64") (pin "1") (pinfunction "1_1") (pintype "passive"))
    )
    (net (code "39") (name "/MISO") (class "Default")
      (node (ref "D1") (pin "6") (pinfunction "C5_6") (pintype "passive"))
      (node (ref "IC2") (pin "21") (pinfunction "PA12/I2C/EIC/SCOM2PAD0+/TC2_21") (pintype "bidirectional"))
      (node (ref "SD-MCU") (pin "7") (pinfunction "DO/D0_7") (pintype "bidirectional"))
    )
    (net (code "40") (name "/MOSI") (class "Default")
      (node (ref "D1") (pin "3") (pinfunction "C2_3") (pintype "passive"))
      (node (ref "IC2") (pin "19") (pinfunction "PB10/EIC/SCOM4PAD2/TC5_19") (pintype "bidirectional"))
      (node (ref "SD-MCU") (pin "3") (pinfunction "DI/CMD_3") (pintype "bidirectional"))
    )
    (net (code "41") (name "/NETLED") (class "Default")
      (node (ref "R16") (pin "2") (pinfunction "2_2") (pintype "passive"))
      (node (ref "U6") (pin "51") (pinfunction "NETLIGHT_51") (pintype "bidirectional"))
    )
    (net (code "42") (name "/PA00_XIN32") (class "Default")
      (node (ref "C5") (pin "1") (pinfunction "1_1") (pintype "passive"))
      (node (ref "IC2") (pin "1") (pinfunction "PA0/XIN32/EIC/SCOM1PAD0/TC2_1") (pintype "bidirectional"))
      (node (ref "X1") (pin "P$2") (pinfunction "P$2_P$2") (pintype "bidirectional"))
    )
    (net (code "43") (name "/PA01_XOUT32") (class "Default")
      (node (ref "C3") (pin "1") (pinfunction "1_1") (pintype "passive"))
      (node (ref "IC2") (pin "2") (pinfunction "PA1/XOUT32/EIC/SCOM1PAD1/TC2_2") (pintype "bidirectional"))
      (node (ref "X1") (pin "P$1") (pinfunction "P$1_P$1") (pintype "bidirectional"))
    )
    (net (code "44") (name "/PCM_CLK") (class "Default")
      (node (ref "R62") (pin "2") (pinfunction "2_2") (pintype "passive"))
      (node (ref "U4") (pin "9") (pinfunction "BCLK_9") (pintype "bidirectional"))
      (node (ref "U6") (pin "76") (pinfunction "PCM_SCLK_76") (pintype "bidirectional"))
    )
    (net (code "45") (name "/PCM_IN") (class "Default")
      (node (ref "U4") (pin "6") (pinfunction "ADCOUT_6") (pintype "bidirectional"))
      (node (ref "U6") (pin "74") (pinfunction "PCM_IN_74") (pintype "bidirectional"))
    )
    (net (code "46") (name "/PCM_OUT") (class "Default")
      (node (ref "U4") (pin "7") (pinfunction "DACIN_7") (pintype "bidirectional"))
      (node (ref "U6") (pin "73") (pinfunction "PCM_OUT_73") (pintype "bidirectional"))
    )
    (net (code "47") (name "/PCM_SYNC") (class "Default")
      (node (ref "U4") (pin "8") (pinfunction "FS_8") (pintype "bidirectional"))
      (node (ref "U6") (pin "75") (pinfunction "PCM_SYNC_75") (pintype "bidirectional"))
    )
    (net (code "48") (name "/RI") (class "Default")
      (node (ref "U6") (pin "69") (pinfunction "RI_69") (pintype "bidirectional"))
      (node (ref "U7") (pin "8") (pinfunction "A7_8") (pintype "bidirectional"))
    )
    (net (code "49") (name "/RTS") (class "Default")
      (node (ref "U6") (pin "66") (pinfunction "RTS_66") (pintype "bidirectional"))
      (node (ref "U7") (pin "4") (pinfunction "A3_4") (pintype "bidirectional"))
    )
    (net (code "50") (name "/RXD") (class "Default")
      (node (ref "Q8") (pin "2") (pinfunction "S_2") (pintype "passive"))
      (node (ref "R28") (pin "1") (pinfunction "1_1") (pintype "passive"))
      (node (ref "U6") (pin "68") (pinfunction "RXD_68") (pintype "bidirectional"))
      (node (ref "U7") (pin "3") (pinfunction "A2_3") (pintype "bidirectional"))
    )
    (net (code "51") (name "/SCK") (class "Default")
      (node (ref "D1") (pin "5") (pinfunction "C4_5") (pintype "passive"))
      (node (ref "IC2") (pin "20") (pinfunction "PB11/EIC/SCOM4PAD3/TC5_20") (pintype "bidirectional"))
      (node (ref "SD-MCU") (pin "5") (pinfunction "CLK_5") (pintype "bidirectional"))
    )
    (net (code "52") (name "/SCL") (class "Default")
      (node (ref "IC2") (pin "32") (pinfunction "PA23/I2C/EIC/SCOM5PAD1+/TC4_32") (pintype "bidirectional"))
      (node (ref "J3") (pin "2") (pinfunction "P$2_2") (pintype "bidirectional"))
      (node (ref "R9") (pin "1") (pinfunction "1_1") (pintype "passive"))
    )
    (net (code "53") (name "/SDA") (class "Default")
      (node (ref "IC2") (pin "31") (pinfunction "PA22/I2C/EIC/SCOM5PAD0+/TC4_31") (pintype "bidirectional"))
      (node (ref "J3") (pin "1") (pinfunction "P$1_1") (pintype "bidirectional"))
      (node (ref "R11") (pin "1") (pinfunction "1_1") (pintype "passive"))
    )
    (net (code "54") (name "/SD_CMD") (class "Default")
      (node (ref "D9") (pin "3") (pinfunction "C2_3") (pintype "passive"))
      (node (ref "SD-LTE") (pin "3") (pinfunction "DI/CMD_3") (pintype "bidirectional"))
      (node (ref "U6") (pin "21") (pinfunction "SD_CMD_21") (pintype "bidirectional"))
    )
    (net (code "55") (name "/SD_DATA0") (class "Default")
      (node (ref "D9") (pin "6") (pinfunction "C5_6") (pintype "passive"))
      (node (ref "SD-LTE") (pin "7") (pinfunction "DO/D0_7") (pintype "bidirectional"))
      (node (ref "U6") (pin "22") (pinfunction "SD_D0_22") (pintype "bidirectional"))
    )
    (net (code "56") (name "/SD_DATA1") (class "Default")
      (node (ref "SD-LTE") (pin "8") (pinfunction "RSV/D1_8") (pintype "bidirectional"))
      (node (ref "U6") (pin "23") (pinfunction "SD_DATA1_23") (pintype "bidirectional"))
    )
    (net (code "57") (name "/SD_DATA2") (class "Default")
      (node (ref "SD-LTE") (pin "1") (pinfunction "RSV/D2_1") (pintype "bidirectional"))
      (node (ref "U6") (pin "24") (pinfunction "SD_DATA2_24") (pintype "bidirectional"))
    )
    (net (code "58") (name "/SD_DATA3") (class "Default")
      (node (ref "D9") (pin "1") (pinfunction "C1_1") (pintype "passive"))
      (node (ref "SD-LTE") (pin "2") (pinfunction "CS/D3_2") (pintype "bidirectional"))
      (node (ref "U6") (pin "25") (pinfunction "SD_DATA3_25") (pintype "bidirectional"))
    )
    (net (code "59") (name "/SD_SCK") (class "Default")
      (node (ref "D9") (pin "5") (pinfunction "C4_5") (pintype "passive"))
      (node (ref "SD-LTE") (pin "5") (pinfunction "CLK_5") (pintype "bidirectional"))
      (node (ref "U6") (pin "26") (pinfunction "SD_CLK_26") (pintype "bidirectional"))
    )
    (net (code "60") (name "/SIM_CLK") (class "Default")
      (node (ref "D10") (pin "4") (pinfunction "C3_4") (pintype "passive"))
      (node (ref "SIM") (pin "3") (pinfunction "CLK_3") (pintype "bidirectional"))
      (node (ref "U6") (pin "19") (pinfunction "USIM_CLK_19") (pintype "bidirectional"))
    )
    (net (code "61") (name "/SIM_DATA") (class "Default")
      (node (ref "D10") (pin "3") (pinfunction "C2_3") (pintype "passive"))
      (node (ref "SIM") (pin "7") (pinfunction "I/O_7") (pintype "bidirectional"))
      (node (ref "U6") (pin "17") (pinfunction "USIM_DATA_17") (pintype "bidirectional"))
    )
    (net (code "62") (name "/SIM_RST") (class "Default")
      (node (ref "D10") (pin "5") (pinfunction "C4_5") (pintype "passive"))
      (node (ref "SIM") (pin "2") (pinfunction "RST_2") (pintype "bidirectional"))
      (node (ref "U6") (pin "18") (pinfunction "USIM_RST_18") (pintype "bidirectional"))
    )
    (net (code "63") (name "/SIM_VDD") (class "Default")
      (node (ref "C52") (pin "2") (pinfunction "2_2") (pintype "passive"))
      (node (ref "D10") (pin "6") (pinfunction "C5_6") (pintype "passive"))
      (node (ref "SIM") (pin "1") (pinfunction "VCC_1") (pintype "bidirectional"))
      (node (ref "U6") (pin "20") (pinfunction "USIM_VDD_20") (pintype "bidirectional"))
    )
    (net (code "64") (name "/SPKOUT_N") (class "Default")
      (node (ref "L7") (pin "1") (pinfunction "1_1") (pintype "passive"))
      (node (ref "U4") (pin "16") (pinfunction "SPKOUT-_16") (pintype "bidirectional"))
    )
    (net (code "65") (name "/SPKOUT_P") (class "Default")
      (node (ref "L6") (pin "1") (pinfunction "1_1") (pintype "passive"))
      (node (ref "U4") (pin "14") (pinfunction "SPKOUT+_14") (pintype "bidirectional"))
    )
    (net (code "66") (name "/SPK_N") (class "Default")
      (node (ref "C30") (pin "2") (pinfunction "2_2") (pintype "passive"))
      (node (ref "C33") (pin "1") (pinfunction "1_1") (pintype "passive"))
      (node (ref "J1") (pin "2") (pinfunction "2_2") (pintype "passive"))
      (node (ref "L7") (pin "2") (pinfunction "2_2") (pintype "passive"))
      (node (ref "SPK") (pin "+") (pinfunction "1_+") (pintype "bidirectional"))
    )
    (net (code "67") (name "/SPK_P") (class "Default")
      (node (ref "C30") (pin "1") (pinfunction "1_1") (pintype "passive"))
      (node (ref "C34") (pin "1") (pinfunction "1_1") (pintype "passive"))
      (node (ref "J1") (pin "1") (pinfunction "1_1") (pintype "passive"))
      (node (ref "L6") (pin "2") (pinfunction "2_2") (pintype "passive"))
      (node (ref "SPK") (pin "-") (pinfunction "2_-") (pintype "bidirectional"))
    )
    (net (code "68") (name "/STATUS") (class "Default")
      (node (ref "R4") (pin "2") (pinfunction "2_2") (pintype "passive"))
      (node (ref "U6") (pin "49") (pinfunction "STATUS_49") (pintype "bidirectional"))
    )
    (net (code "69") (name "/SWCLK") (class "Default")
      (node (ref "CN2") (pin "4") (pinfunction "4_4") (pintype "passive"))
      (node (ref "IC2") (pin "45") (pinfunction "PA30/EIC/SCOM1PAD2/TC1_45") (pintype "bidirectional"))
    )
    (net (code "70") (name "/SWDIO") (class "Default")
      (node (ref "CN2") (pin "2") (pinfunction "2_2") (pintype "passive"))
      (node (ref "IC2") (pin "46") (pinfunction "PA31/EIC/SCOM1PAD3/TC1_46") (pintype "bidirectional"))
    )
    (net (code "71") (name "/TXD") (class "Default")
      (node (ref "Q7") (pin "2") (pinfunction "S_2") (pintype "passive"))
      (node (ref "R27") (pin "1") (pinfunction "1_1") (pintype "passive"))
      (node (ref "U6") (pin "71") (pinfunction "TXD_71") (pintype "bidirectional"))
      (node (ref "U7") (pin "1") (pinfunction "A1_1") (pintype "bidirectional"))
    )
    (net (code "72") (name "/V4D2") (class "Default")
      (node (ref "C21") (pin "2") (pinfunction "2_2") (pintype "passive"))
      (node (ref "C26") (pin "2") (pinfunction "2_2") (pintype "passive"))
      (node (ref "C27") (pin "2") (pinfunction "2_2") (pintype "passive"))
      (node (ref "D11") (pin "A") (pinfunction "A_A") (pintype "passive"))
      (node (ref "L5") (pin "2") (pinfunction "2_2") (pintype "passive"))
      (node (ref "Q2") (pin "1") (pinfunction "G_1") (pintype "passive"))
      (node (ref "R15") (pin "1") (pinfunction "1_1") (pintype "passive"))
      (node (ref "R42") (pin "2") (pinfunction "2_2") (pintype "passive"))
      (node (ref "U3") (pin "5") (pinfunction "OUT_5") (pintype "bidirectional"))
    )
    (net (code "73") (name "/VBAT-") (class "Default")
      (node (ref "BAT") (pin "1") (pinfunction "1_1") (pintype "bidirectional"))
      (node (ref "C25") (pin "1") (pinfunction "1_1") (pintype "passive"))
      (node (ref "J4") (pin "2") (pinfunction "2_2") (pintype "passive"))
      (node (ref "R22") (pin "1") (pinfunction "1_1") (pintype "passive"))
      (node (ref "U1") (pin "3") (pinfunction "S2_3") (pintype "bidirectional"))
      (node (ref "U1") (pin "6") (pinfunction "VSS_6") (pintype "bidirectional"))
    )
    (net (code "74") (name "/VBAT_IN") (class "Default")
      (node (ref "D4") (pin "A") (pinfunction "A_A") (pintype "passive"))
      (node (ref "Q2") (pin "3") (pinfunction "D_3") (pintype "passive"))
      (node (ref "R5") (pin "2") (pinfunction "2_2") (pintype "passive"))
      (node (ref "SW1") (pin "CH1A") (pinfunction "CH1A_CH1A") (pintype "bidirectional"))
    )
    (net (code "75") (name "/VDDCORE") (class "Default")
      (node (ref "C7") (pin "1") (pinfunction "1_1") (pintype "passive"))
      (node (ref "IC2") (pin "43") (pinfunction "VDDCORE1_43") (pintype "input"))
    )
    (net (code "76") (name "/VIN") (class "Default")
      (node (ref "C10") (pin "2") (pinfunction "2_2") (pintype "passive"))
      (node (ref "C17") (pin "2") (pinfunction "2_2") (pintype "passive"))
      (node (ref "D11") (pin "C") (pinfunction "C_C") (pintype "passive"))
      (node (ref "D4") (pin "C") (pinfunction "C_C") (pintype "passive"))
      (node (ref "Q2") (pin "2") (pinfunction "S_2") (pintype "passive"))
      (node (ref "R19") (pin "2") (pinfunction "2_2") (pintype "passive"))
      (node (ref "R45") (pin "2") (pinfunction "2_2") (pintype "passive"))
      (node (ref "U8") (pin "1") (pinfunction "VIN_1") (pintype "bidirectional"))
      (node (ref "U8") (pin "3") (pinfunction "EN_3") (pintype "bidirectional"))
    )
    (net (code "77") (name "/VSYS") (class "Default")
      (node (ref "C28") (pin "2") (pinfunction "2_2") (pintype "passive"))
      (node (ref "C31") (pin "2") (pinfunction "2_2") (pintype "passive"))
      (node (ref "R10") (pin "2") (pinfunction "2_2") (pintype "passive"))
      (node (ref "R43") (pin "2") (pinfunction "2_2") (pintype "passive"))
      (node (ref "R44") (pin "2") (pinfunction "2_2") (pintype "passive"))
      (node (ref "SW1") (pin "CH2A") (pinfunction "CH2A_CH2A") (pintype "bidirectional"))
      (node (ref "U3") (pin "2") (pinfunction "VIN_2") (pintype "bidirectional"))
    )
    (net (code "78") (name "/VUSB") (class "Default")
      (node (ref "D2") (pin "A") (pinfunction "A_A") (pintype "passive"))
      (node (ref "U6") (pin "11") (pinfunction "USB_VBUS_11") (pintype "bidirectional"))
      (node (ref "USB-LTE") (pin "VBUS1") (pinfunction "VBUS_VBUS1") (pintype "bidirectional"))
      (node (ref "USB-LTE") (pin "VBUS2") (pinfunction "VBUS_VBUS2") (pintype "bidirectional"))
    )
    (net (code "79") (name "1.8V") (class "Default")
      (node (ref "C49") (pin "2") (pinfunction "2_2") (pintype "passive"))
      (node (ref "L3") (pin "1") (pinfunction "1_1") (pintype "passive"))
      (node (ref "Q7") (pin "1") (pinfunction "G_1") (pintype "passive"))
      (node (ref "Q8") (pin "1") (pinfunction "G_1") (pintype "passive"))
      (node (ref "R27") (pin "2") (pinfunction "2_2") (pintype "passive"))
      (node (ref "R28") (pin "2") (pinfunction "2_2") (pintype "passive"))
      (node (ref "R41") (pin "1") (pinfunction "1_1") (pintype "passive"))
      (node (ref "R55") (pin "1") (pinfunction "1_1") (pintype "passive"))
      (node (ref "R58") (pin "2") (pinfunction "2_2") (pintype "passive"))
      (node (ref "TP6") (pin "P$1") (pinfunction "1_P$1") (pintype "bidirectional"))
      (node (ref "U6") (pin "15") (pinfunction "VDD_1V8_15") (pintype "bidirectional"))
      (node (ref "U7") (pin "10") (pinfunction "OE_10") (pintype "bidirectional"))
      (node (ref "U7") (pin "2") (pinfunction "VCCA_2") (pintype "bidirectional"))
    )
    (net (code "80") (name "AGND") (class "Default")
      (node (ref "C13") (pin "2") (pinfunction "2_2") (pintype "passive"))
      (node (ref "C14") (pin "1") (pinfunction "1_1") (pintype "passive"))
      (node (ref "C16") (pin "1") (pinfunction "1_1") (pintype "passive"))
      (node (ref "C20") (pin "1") (pinfunction "1_1") (pintype "passive"))
      (node (ref "C53") (pin "1") (pinfunction "1_1") (pintype "passive"))
      (node (ref "C54") (pin "1") (pinfunction "1_1") (pintype "passive"))
      (node (ref "C55") (pin "1") (pinfunction "1_1") (pintype "passive"))
      (node (ref "C56") (pin "1") (pinfunction "1_1") (pintype "passive"))
      (node (ref "C57") (pin "1") (pinfunction "1_1") (pintype "passive"))
      (node (ref "C58") (pin "1") (pinfunction "1_1") (pintype "passive"))
      (node (ref "C59") (pin "1") (pinfunction "1_1") (pintype "passive"))
      (node (ref "C60") (pin "1") (pinfunction "1_1") (pintype "passive"))
      (node (ref "C61") (pin "1") (pinfunction "1_1") (pintype "passive"))
      (node (ref "C62") (pin "1") (pinfunction "1_1") (pintype "passive"))
      (node (ref "C63") (pin "1") (pinfunction "1_1") (pintype "passive"))
      (node (ref "C64") (pin "1") (pinfunction "1_1") (pintype "passive"))
      (node (ref "C67") (pin "1") (pinfunction "1_1") (pintype "passive"))
      (node (ref "C68") (pin "1") (pinfunction "1_1") (pintype "passive"))
      (node (ref "C69") (pin "1") (pinfunction "1_1") (pintype "passive"))
      (node (ref "C70") (pin "1") (pinfunction "1_1") (pintype "passive"))
      (node (ref "C79") (pin "1") (pinfunction "1_1") (pintype "passive"))
      (node (ref "C80") (pin "2") (pinfunction "2_2") (pintype "passive"))
      (node (ref "C82") (pin "2") (pinfunction "2_2") (pintype "passive"))
      (node (ref "C83") (pin "1") (pinfunction "1_1") (pintype "passive"))
      (node (ref "C9") (pin "1") (pinfunction "1_1") (pintype "passive"))
      (node (ref "R61") (pin "2") (pinfunction "2_2") (pintype "passive"))
      (node (ref "R63") (pin "1") (pinfunction "1_1") (pintype "passive"))
      (node (ref "U4") (pin "15") (pinfunction "VSSSPK_15") (pintype "bidirectional"))
      (node (ref "U4") (pin "21") (pinfunction "PAD_21") (pintype "bidirectional"))
      (node (ref "U4") (pin "3") (pinfunction "VSSA_3") (pintype "bidirectional"))
      (node (ref "U4") (pin "5") (pinfunction "VSSD_5") (pintype "bidirectional"))
    )
    (net (code "81") (name "D+") (class "Default")
      (node (ref "IC2") (pin "34") (pinfunction "PA25/EIC/SCOM3PAD3+/TC5_34") (pintype "bidirectional"))
      (node (ref "USB-MCU") (pin "A6") (pinfunction "D+_A6") (pintype "bidirectional"))
      (node (ref "USB-MCU") (pin "B6") (pinfunction "D+_B6") (pintype "bidirectional"))
    )
    (net (code "82") (name "D-") (class "Default")
      (node (ref "IC2") (pin "33") (pinfunction "PA24/EIC/SCOM3PAD2+/TC5_33") (pintype "bidirectional"))
      (node (ref "USB-MCU") (pin "A7") (pinfunction "D-_A7") (pintype "bidirectional"))
      (node (ref "USB-MCU") (pin "B7") (pinfunction "D-_B7") (pintype "bidirectional"))
    )
    (net (code "83") (name "GND") (class "Default")
      (node (ref "C1") (pin "2") (pinfunction "2_2") (pintype "passive"))
      (node (ref "C10") (pin "1") (pinfunction "1_1") (pintype "passive"))
      (node (ref "C11") (pin "1") (pinfunction "1_1") (pintype "passive"))
      (node (ref "C12") (pin "1") (pinfunction "1_1") (pintype "passive"))
      (node (ref "C15") (pin "2") (pinfunction "2_2") (pintype "passive"))
      (node (ref "C17") (pin "1") (pinfunction "1_1") (pintype "passive"))
      (node (ref "C18") (pin "2") (pinfunction "2_2") (pintype "passive"))
      (node (ref "C19") (pin "1") (pinfunction "1_1") (pintype "passive"))
      (node (ref "C2") (pin "1") (pinfunction "1_1") (pintype "passive"))
      (node (ref "C21") (pin "1") (pinfunction "1_1") (pintype "passive"))
      (node (ref "C22") (pin "2") (pinfunction "2_2") (pintype "passive"))
      (node (ref "C23") (pin "2") (pinfunction "2_2") (pintype "passive"))
      (node (ref "C26") (pin "1") (pinfunction "1_1") (pintype "passive"))
      (node (ref "C28") (pin "1") (pinfunction "1_1") (pintype "passive"))
      (node (ref "C3") (pin "2") (pinfunction "2_2") (pintype "passive"))
      (node (ref "C31") (pin "1") (pinfunction "1_1") (pintype "passive"))
      (node (ref "C33") (pin "2") (pinfunction "2_2") (pintype "passive"))
      (node (ref "C34") (pin "2") (pinfunction "2_2") (pintype "passive"))
      (node (ref "C36") (pin "1") (pinfunction "1_1") (pintype "passive"))
      (node (ref "C4") (pin "2") (pinfunction "2_2") (pintype "passive"))
      (node (ref "C41") (pin "1") (pinfunction "1_1") (pintype "passive"))
      (node (ref "C42") (pin "1") (pinfunction "1_1") (pintype "passive"))
      (node (ref "C43") (pin "1") (pinfunction "1_1") (pintype "passive"))
      (node (ref "C44") (pin "2") (pinfunction "2_2") (pintype "passive"))
      (node (ref "C46") (pin "1") (pinfunction "1_1") (pintype "passive"))
      (node (ref "C47") (pin "1") (pinfunction "1_1") (pintype "passive"))
      (node (ref "C48") (pin "C") (pinfunction "-_C") (pintype "passive"))
      (node (ref "C49") (pin "1") (pinfunction "1_1") (pintype "passive"))
      (node (ref "C5") (pin "2") (pinfunction "2_2") (pintype "passive"))
      (node (ref "C50") (pin "1") (pinfunction "1_1") (pintype "passive"))
      (node (ref "C51") (pin "2") (pinfunction "2_2") (pintype "passive"))
      (node (ref "C52") (pin "1") (pinfunction "1_1") (pintype "passive"))
      (node (ref "C6") (pin "2") (pinfunction "2_2") (pintype "passive"))
      (node (ref "C7") (pin "2") (pinfunction "2_2") (pintype "passive"))
      (node (ref "C8") (pin "1") (pinfunction "1_1") (pintype "passive"))
      (node (ref "CN2") (pin "3") (pinfunction "3_3") (pintype "passive"))
      (node (ref "CN2") (pin "5") (pinfunction "5_5") (pintype "passive"))
      (node (ref "CN2") (pin "9") (pinfunction "9_9") (pintype "passive"))
      (node (ref "D1") (pin "2") (pinfunction "A_2") (pintype "passive"))
      (node (ref "D10") (pin "2") (pinfunction "A_2") (pintype "passive"))
      (node (ref "D8") (pin "A") (pinfunction "A_A") (pintype "passive"))
      (node (ref "D9") (pin "2") (pinfunction "A_2") (pintype "passive"))
      (node (ref "GPS") (pin "GND1") (pinfunction "GND1_GND1") (pintype "bidirectional"))
      (node (ref "GPS") (pin "GND2") (pinfunction "GND2_GND2") (pintype "bidirectional"))
      (node (ref "GPS") (pin "GND3") (pinfunction "GND3_GND3") (pintype "bidirectional"))
      (node (ref "IC2") (pin "18") (pinfunction "GND1_18") (pintype "power_in"))
      (node (ref "IC2") (pin "35") (pinfunction "GND2_35") (pintype "power_in"))
      (node (ref "IC2") (pin "42") (pinfunction "GND3_42") (pintype "power_in"))
      (node (ref "IC2") (pin "5") (pinfunction "GNDANA_5") (pintype "power_in"))
      (node (ref "J2") (pin "10") (pinfunction "10_10") (pintype "bidirectional"))
      (node (ref "J3") (pin "4") (pinfunction "P$4_4") (pintype "bidirectional"))
      (node (ref "LET_A") (pin "GND1") (pinfunction "GND1_GND1") (pintype "bidirectional"))
      (node (ref "LET_A") (pin "GND2") (pinfunction "GND2_GND2") (pintype "bidirectional"))
      (node (ref "LET_A") (pin "GND3") (pinfunction "GND3_GND3") (pintype "bidirectional"))
      (node (ref "LTE_M") (pin "GND1") (pinfunction "GND1_GND1") (pintype "bidirectional"))
      (node (ref "LTE_M") (pin "GND2") (pinfunction "GND2_GND2") (pintype "bidirectional"))
      (node (ref "LTE_M") (pin "GND3") (pinfunction "GND3_GND3") (pintype "bidirectional"))
      (node (ref "PWK") (pin "1") (pinfunction "1_1") (pintype "passive"))
      (node (ref "PWR") (pin "-") (pinfunction "-_-") (pintype "passive"))
      (node (ref "Q1") (pin "2") (pinfunction "S_2") (pintype "passive"))
      (node (ref "Q3") (pin "2") (pinfunction "S_2") (pintype "passive"))
      (node (ref "Q4") (pin "2") (pinfunction "S_2") (pintype "passive"))
      (node (ref "Q5") (pin "2") (pinfunction "S_2") (pintype "passive"))
      (node (ref "Q6") (pin "2") (pinfunction "S_2") (pintype "passive"))
      (node (ref "R14") (pin "1") (pinfunction "1_1") (pintype "passive"))
      (node (ref "R15") (pin "2") (pinfunction "2_2") (pintype "passive"))
      (node (ref "R2") (pin "1") (pinfunction "1_1") (pintype "passive"))
      (node (ref "R20") (pin "1") (pinfunction "1_1") (pintype "passive"))
      (node (ref "R22") (pin "2") (pinfunction "2_2") (pintype "passive"))
      (node (ref "R23") (pin "1") (pinfunction "1_1") (pintype "passive"))
      (node (ref "R24") (pin "2") (pinfunction "2_2") (pintype "passive"))
      (node (ref "R25") (pin "2") (pinfunction "2_2") (pintype "passive"))
      (node (ref "R26") (pin "2") (pinfunction "2_2") (pintype "passive"))
      (node (ref "R29") (pin "1") (pinfunction "1_1") (pintype "passive"))
      (node (ref "R3") (pin "1") (pinfunction "1_1") (pintype "passive"))
      (node (ref "R30") (pin "2") (pinfunction "2_2") (pintype "passive"))
      (node (ref "R36") (pin "1") (pinfunction "1_1") (pintype "passive"))
      (node (ref "R38") (pin "1") (pinfunction "1_1") (pintype "passive"))
      (node (ref "R46") (pin "2") (pinfunction "2_2") (pintype "passive"))
      (node (ref "R48") (pin "2") (pinfunction "2_2") (pintype "passive"))
      (node (ref "R56") (pin "1") (pinfunction "1_1") (pintype "passive"))
      (node (ref "R61") (pin "1") (pinfunction "1_1") (pintype "passive"))
      (node (ref "R67") (pin "1") (pinfunction "1_1") (pintype "passive"))
      (node (ref "R8") (pin "1") (pinfunction "1_1") (pintype "passive"))
      (node (ref "RESET") (pin "P$2") (pinfunction "2_P$2") (pintype "bidirectional"))
      (node (ref "SD-LTE") (pin "10") (pinfunction "G2_10") (pintype "bidirectional"))
      (node (ref "SD-LTE") (pin "11") (pinfunction "G3_11") (pintype "bidirectional"))
      (node (ref "SD-LTE") (pin "12") (pinfunction "G4_12") (pintype "bidirectional"))
      (node (ref "SD-LTE") (pin "6") (pinfunction "VSS_6") (pintype "bidirectional"))
      (node (ref "SD-LTE") (pin "9") (pinfunction "G1_9") (pintype "bidirectional"))
      (node (ref "SD-MCU") (pin "10") (pinfunction "G2_10") (pintype "bidirectional"))
      (node (ref "SD-MCU") (pin "11") (pinfunction "G3_11") (pintype "bidirectional"))
      (node (ref "SD-MCU") (pin "12") (pinfunction "G4_12") (pintype "bidirectional"))
      (node (ref "SD-MCU") (pin "6") (pinfunction "VSS_6") (pintype "bidirectional"))
      (node (ref "SD-MCU") (pin "9") (pinfunction "G1_9") (pintype "bidirectional"))
      (node (ref "SIM") (pin "5") (pinfunction "GND_5") (pintype "bidirectional"))
      (node (ref "SPK") (pin "3") (pinfunction "3_3") (pintype "bidirectional"))
      (node (ref "SPK") (pin "4") (pinfunction "4_4") (pintype "bidirectional"))
      (node (ref "U1") (pin "2") (pinfunction "S1_2") (pintype "bidirectional"))
      (node (ref "U2") (pin "1") (pinfunction "TEMP_1") (pintype "bidirectional"))
      (node (ref "U2") (pin "3") (pinfunction "GND_3") (pintype "bidirectional"))
      (node (ref "U2") (pin "9") (pinfunction "GND_9") (pintype "bidirectional"))
      (node (ref "U3") (pin "4") (pinfunction "PGND_4") (pintype "bidirectional"))
      (node (ref "U3") (pin "6") (pinfunction "AGND_6") (pintype "bidirectional"))
      (node (ref "U6") (pin "1") (pinfunction "GND1_1") (pintype "bidirectional"))
      (node (ref "U6") (pin "10") (pinfunction "GND4_10") (pintype "bidirectional"))
      (node (ref "U6") (pin "14") (pinfunction "GND5_14") (pintype "bidirectional"))
      (node (ref "U6") (pin "2") (pinfunction "GND2_2") (pintype "bidirectional"))
      (node (ref "U6") (pin "37") (pinfunction "GND6_37") (pintype "bidirectional"))
      (node (ref "U6") (pin "40") (pinfunction "GND7_40") (pintype "bidirectional"))
      (node (ref "U6") (pin "41") (pinfunction "GND8_41") (pintype "bidirectional"))
      (node (ref "U6") (pin "43") (pinfunction "GND9_43") (pintype "bidirectional"))
      (node (ref "U6") (pin "5") (pinfunction "GND3_5") (pintype "bidirectional"))
      (node (ref "U6") (pin "57") (pinfunction "GND10_57") (pintype "bidirectional"))
      (node (ref "U6") (pin "58") (pinfunction "GND11_58") (pintype "bidirectional"))
      (node (ref "U6") (pin "60") (pinfunction "GND12_60") (pintype "bidirectional"))
      (node (ref "U6") (pin "61") (pinfunction "GND13_61") (pintype "bidirectional"))
      (node (ref "U6") (pin "64") (pinfunction "GND14_64") (pintype "bidirectional"))
      (node (ref "U6") (pin "65") (pinfunction "GND15_65") (pintype "bidirectional"))
      (node (ref "U6") (pin "77") (pinfunction "GND16_77") (pintype "bidirectional"))
      (node (ref "U6") (pin "78") (pinfunction "GND17_78") (pintype "bidirectional"))
      (node (ref "U6") (pin "80") (pinfunction "GND18_80") (pintype "bidirectional"))
      (node (ref "U6") (pin "81") (pinfunction "GND19_81") (pintype "bidirectional"))
      (node (ref "U7") (pin "11") (pinfunction "GND_11") (pintype "bidirectional"))
      (node (ref "U8") (pin "2") (pinfunction "GND_2") (pintype "bidirectional"))
      (node (ref "USB-LTE") (pin "GND") (pinfunction "GND_GND") (pintype "bidirectional"))
      (node (ref "USB-LTE") (pin "GND2") (pinfunction "GND_GND2") (pintype "bidirectional"))
      (node (ref "USB-LTE") (pin "SHLD1") (pinfunction "SHLD_SHLD1") (pintype "bidirectional"))
      (node (ref "USB-LTE") (pin "SHLD2") (pinfunction "SHLD_SHLD2") (pintype "bidirectional"))
      (node (ref "USB-LTE") (pin "SHLD3") (pinfunction "SHLD_SHLD3") (pintype "bidirectional"))
      (node (ref "USB-LTE") (pin "SHLD4") (pinfunction "SHLD_SHLD4") (pintype "bidirectional"))
      (node (ref "USB-LTE") (pin "SHLD5") (pinfunction "SHLD_SHLD5") (pintype "bidirectional"))
      (node (ref "USB-LTE") (pin "SHLD6") (pinfunction "SHLD_SHLD6") (pintype "bidirectional"))
      (node (ref "USB-LTE") (pin "SHLD7") (pinfunction "SHLD_SHLD7") (pintype "bidirectional"))
      (node (ref "USB-LTE") (pin "SHLD8") (pinfunction "SHLD_SHLD8") (pintype "bidirectional"))
      (node (ref "USB-MCU") (pin "GND") (pinfunction "GND_GND") (pintype "bidirectional"))
      (node (ref "USB-MCU") (pin "GND2") (pinfunction "GND_GND2") (pintype "bidirectional"))
      (node (ref "USB-MCU") (pin "SHLD1") (pinfunction "SHLD_SHLD1") (pintype "bidirectional"))
      (node (ref "USB-MCU") (pin "SHLD2") (pinfunction "SHLD_SHLD2") (pintype "bidirectional"))
      (node (ref "USB-MCU") (pin "SHLD3") (pinfunction "SHLD_SHLD3") (pintype "bidirectional"))
      (node (ref "USB-MCU") (pin "SHLD4") (pinfunction "SHLD_SHLD4") (pintype "bidirectional"))
      (node (ref "USB-MCU") (pin "SHLD5") (pinfunction "SHLD_SHLD5") (pintype "bidirectional"))
      (node (ref "USB-MCU") (pin "SHLD6") (pinfunction "SHLD_SHLD6") (pintype "bidirectional"))
      (node (ref "USB-MCU") (pin "SHLD7") (pinfunction "SHLD_SHLD7") (pintype "bidirectional"))
      (node (ref "USB-MCU") (pin "SHLD8") (pinfunction "SHLD_SHLD8") (pintype "bidirectional"))
      (node (ref "VLTE") (pin "C") (pinfunction "C_C") (pintype "passive"))
    )
    (net (code "84") (name "Net-(C16-Pad2)") (class "Default")
      (node (ref "C16") (pin "2") (pinfunction "2_2") (pintype "passive"))
      (node (ref "R17") (pin "1") (pinfunction "1_1") (pintype "passive"))
      (node (ref "R33") (pin "1") (pinfunction "1_1") (pintype "passive"))
      (node (ref "R37") (pin "1") (pinfunction "1_1") (pintype "passive"))
    )
    (net (code "85") (name "Net-(C20-Pad2)") (class "Default")
      (node (ref "C20") (pin "2") (pinfunction "2_2") (pintype "passive"))
      (node (ref "FB3") (pin "2") (pinfunction "2_2") (pintype "passive"))
      (node (ref "R33") (pin "2") (pinfunction "2_2") (pintype "passive"))
    )
    (net (code "86") (name "Net-(C41-Pad2)") (class "Default")
      (node (ref "C41") (pin "2") (pinfunction "2_2") (pintype "passive"))
      (node (ref "LTE_M") (pin "D") (pinfunction "D_D") (pintype "bidirectional"))
      (node (ref "R34") (pin "2") (pinfunction "2_2") (pintype "passive"))
    )
    (net (code "87") (name "Net-(C43-Pad2)") (class "Default")
      (node (ref "C43") (pin "2") (pinfunction "2_2") (pintype "passive"))
      (node (ref "LET_A") (pin "D") (pinfunction "D_D") (pintype "bidirectional"))
      (node (ref "R39") (pin "2") (pinfunction "2_2") (pintype "passive"))
    )
    (net (code "88") (name "Net-(C44-Pad1)") (class "Default")
      (node (ref "C44") (pin "1") (pinfunction "1_1") (pintype "passive"))
      (node (ref "L1") (pin "1") (pinfunction "1_1") (pintype "passive"))
      (node (ref "R40") (pin "1") (pinfunction "1_1") (pintype "passive"))
    )
    (net (code "89") (name "Net-(C45-Pad1)") (class "Default")
      (node (ref "C45") (pin "1") (pinfunction "1_1") (pintype "passive"))
      (node (ref "GPS") (pin "D") (pinfunction "D_D") (pintype "bidirectional"))
      (node (ref "L1") (pin "2") (pinfunction "2_2") (pintype "passive"))
    )
    (net (code "90") (name "Net-(C78-Pad1)") (class "Default")
      (node (ref "C78") (pin "1") (pinfunction "1_1") (pintype "passive"))
      (node (ref "C79") (pin "2") (pinfunction "2_2") (pintype "passive"))
      (node (ref "C81") (pin "1") (pinfunction "1_1") (pintype "passive"))
      (node (ref "C83") (pin "2") (pinfunction "2_2") (pintype "passive"))
      (node (ref "EAR") (pin "4") (pinfunction "4_4") (pintype "bidirectional"))
      (node (ref "R66") (pin "1") (pinfunction "1_1") (pintype "passive"))
    )
    (net (code "91") (name "Net-(C78-Pad2)") (class "Default")
      (node (ref "C78") (pin "2") (pinfunction "2_2") (pintype "passive"))
      (node (ref "C80") (pin "1") (pinfunction "1_1") (pintype "passive"))
      (node (ref "C81") (pin "2") (pinfunction "2_2") (pintype "passive"))
      (node (ref "C82") (pin "1") (pinfunction "1_1") (pintype "passive"))
      (node (ref "EAR") (pin "3") (pinfunction "3_3") (pintype "bidirectional"))
      (node (ref "R65") (pin "1") (pinfunction "1_1") (pintype "passive"))
    )
    (net (code "92") (name "Net-(CHG-Pad1)") (class "Default")
      (node (ref "CHG") (pin "1") (pinfunction "1_1") (pintype "bidirectional"))
      (node (ref "R31") (pin "1") (pinfunction "1_1") (pintype "passive"))
    )
    (net (code "93") (name "Net-(CHG-Pad3)") (class "Default")
      (node (ref "CHG") (pin "3") (pinfunction "3_3") (pintype "bidirectional"))
      (node (ref "R32") (pin "1") (pinfunction "1_1") (pintype "passive"))
    )
    (net (code "94") (name "Net-(EAR-Pad1)") (class "Default")
      (node (ref "EAR") (pin "1") (pinfunction "1_1") (pintype "bidirectional"))
      (node (ref "R30") (pin "1") (pinfunction "1_1") (pintype "passive"))
      (node (ref "R37") (pin "2") (pinfunction "2_2") (pintype "passive"))
    )
    (net (code "95") (name "Net-(EAR-Pad2)") (class "Default")
      (node (ref "EAR") (pin "2") (pinfunction "2_2") (pintype "bidirectional"))
      (node (ref "R17") (pin "2") (pinfunction "2_2") (pintype "passive"))
      (node (ref "R25") (pin "1") (pinfunction "1_1") (pintype "passive"))
    )
    (net (code "96") (name "Net-(FB1-Pad2)") (class "Default")
      (node (ref "FB1") (pin "2") (pinfunction "2_2") (pintype "passive"))
      (node (ref "R65") (pin "2") (pinfunction "2_2") (pintype "passive"))
    )
    (net (code "97") (name "Net-(FB2-Pad2)") (class "Default")
      (node (ref "FB2") (pin "2") (pinfunction "2_2") (pintype "passive"))
      (node (ref "R66") (pin "2") (pinfunction "2_2") (pintype "passive"))
    )
    (net (code "98") (name "Net-(NET-PadA)") (class "Default")
      (node (ref "NET") (pin "A") (pinfunction "A_A") (pintype "passive"))
      (node (ref "R18") (pin "1") (pinfunction "1_1") (pintype "passive"))
    )
    (net (code "99") (name "Net-(PWR-Pad+)") (class "Default")
      (node (ref "PWR") (pin "+") (pinfunction "+_+") (pintype "passive"))
      (node (ref "R7") (pin "2") (pinfunction "2_2") (pintype "passive"))
    )
    (net (code "100") (name "Net-(Q1-D)") (class "Default")
      (node (ref "Q1") (pin "3") (pinfunction "D_3") (pintype "passive"))
      (node (ref "STA") (pin "C") (pinfunction "C_C") (pintype "passive"))
    )
    (net (code "101") (name "Net-(Q1-G)") (class "Default")
      (node (ref "Q1") (pin "1") (pinfunction "G_1") (pintype "passive"))
      (node (ref "R3") (pin "2") (pinfunction "2_2") (pintype "passive"))
      (node (ref "R4") (pin "1") (pinfunction "1_1") (pintype "passive"))
    )
    (net (code "102") (name "Net-(Q3-D)") (class "Default")
      (node (ref "PWK") (pin "2") (pinfunction "2_2") (pintype "passive"))
      (node (ref "Q3") (pin "3") (pinfunction "D_3") (pintype "passive"))
      (node (ref "U6") (pin "3") (pinfunction "PWRKEY_3") (pintype "bidirectional"))
    )
    (net (code "103") (name "Net-(Q3-G)") (class "Default")
      (node (ref "Q3") (pin "1") (pinfunction "G_1") (pintype "passive"))
      (node (ref "R35") (pin "1") (pinfunction "1_1") (pintype "passive"))
      (node (ref "R36") (pin "2") (pinfunction "2_2") (pintype "passive"))
    )
    (net (code "104") (name "Net-(Q4-G)") (class "Default")
      (node (ref "Q4") (pin "1") (pinfunction "G_1") (pintype "passive"))
      (node (ref "R56") (pin "2") (pinfunction "2_2") (pintype "passive"))
      (node (ref "R57") (pin "1") (pinfunction "1_1") (pintype "passive"))
    )
    (net (code "105") (name "Net-(Q5-D)") (class "Default")
      (node (ref "Q5") (pin "3") (pinfunction "D_3") (pintype "passive"))
      (node (ref "U6") (pin "4") (pinfunction "RESET_4") (pintype "bidirectional"))
    )
    (net (code "106") (name "Net-(Q5-G)") (class "Default")
      (node (ref "Q5") (pin "1") (pinfunction "G_1") (pintype "passive"))
      (node (ref "R67") (pin "2") (pinfunction "2_2") (pintype "passive"))
      (node (ref "R68") (pin "1") (pinfunction "1_1") (pintype "passive"))
    )
    (net (code "107") (name "Net-(Q6-D)") (class "Default")
      (node (ref "NET") (pin "C") (pinfunction "C_C") (pintype "passive"))
      (node (ref "Q6") (pin "3") (pinfunction "D_3") (pintype "passive"))
    )
    (net (code "108") (name "Net-(Q6-G)") (class "Default")
      (node (ref "Q6") (pin "1") (pinfunction "G_1") (pintype "passive"))
      (node (ref "R14") (pin "2") (pinfunction "2_2") (pintype "passive"))
      (node (ref "R16") (pin "1") (pinfunction "1_1") (pintype "passive"))
    )
    (net (code "109") (name "Net-(R6-Pad1)") (class "Default")
      (node (ref "R6") (pin "1") (pinfunction "1_1") (pintype "passive"))
      (node (ref "STA") (pin "A") (pinfunction "A_A") (pintype "passive"))
    )
    (net (code "110") (name "Net-(R60-Pad1)") (class "Default")
      (node (ref "R60") (pin "1") (pinfunction "1_1") (pintype "passive"))
      (node (ref "VLTE") (pin "A") (pinfunction "A_A") (pintype "passive"))
    )
    (net (code "111") (name "Net-(TP5-1)") (class "Default")
      (node (ref "TP5") (pin "P$1") (pinfunction "1_P$1") (pintype "bidirectional"))
      (node (ref "U6") (pin "85") (pinfunction "BOOT_CFG0_85") (pintype "bidirectional"))
    )
    (net (code "112") (name "Net-(U1-V)") (class "Default")
      (node (ref "R20") (pin "2") (pinfunction "2_2") (pintype "passive"))
      (node (ref "U1") (pin "1") (pinfunction "V_1") (pintype "bidirectional"))
    )
    (net (code "113") (name "Net-(U1-VDD)") (class "Default")
      (node (ref "C25") (pin "2") (pinfunction "2_2") (pintype "passive"))
      (node (ref "R21") (pin "2") (pinfunction "2_2") (pintype "passive"))
      (node (ref "U1") (pin "5") (pinfunction "VDD_5") (pintype "bidirectional"))
    )
    (net (code "114") (name "Net-(U2-CHRG)") (class "Default")
      (node (ref "R31") (pin "2") (pinfunction "2_2") (pintype "passive"))
      (node (ref "U2") (pin "7") (pinfunction "CHRG_7") (pintype "bidirectional"))
    )
    (net (code "115") (name "Net-(U2-DONE)") (class "Default")
      (node (ref "R32") (pin "2") (pinfunction "2_2") (pintype "passive"))
      (node (ref "U2") (pin "6") (pinfunction "DONE_6") (pintype "bidirectional"))
    )
    (net (code "116") (name "Net-(U2-ISET)") (class "Default")
      (node (ref "R29") (pin "2") (pinfunction "2_2") (pintype "passive"))
      (node (ref "U2") (pin "2") (pinfunction "ISET_2") (pintype "bidirectional"))
    )
    (net (code "117") (name "Net-(U3-EN)") (class "Default")
      (node (ref "R44") (pin "1") (pinfunction "1_1") (pintype "passive"))
      (node (ref "U3") (pin "8") (pinfunction "EN_8") (pintype "bidirectional"))
    )
    (net (code "118") (name "Net-(U3-FB)") (class "Default")
      (node (ref "C27") (pin "1") (pinfunction "1_1") (pintype "passive"))
      (node (ref "R38") (pin "2") (pinfunction "2_2") (pintype "passive"))
      (node (ref "R42") (pin "1") (pinfunction "1_1") (pintype "passive"))
      (node (ref "U3") (pin "7") (pinfunction "FB_7") (pintype "bidirectional"))
    )
    (net (code "119") (name "Net-(U3-PG)") (class "Default")
      (node (ref "R43") (pin "1") (pinfunction "1_1") (pintype "passive"))
      (node (ref "U3") (pin "1") (pinfunction "PG_1") (pintype "bidirectional"))
    )
    (net (code "120") (name "Net-(U3-SW)") (class "Default")
      (node (ref "L5") (pin "1") (pinfunction "1_1") (pintype "passive"))
      (node (ref "U3") (pin "3") (pinfunction "SW_3") (pintype "bidirectional"))
    )
    (net (code "121") (name "Net-(U4-MC+)") (class "Default")
      (node (ref "C72") (pin "2") (pinfunction "2_2") (pintype "passive"))
      (node (ref "U4") (pin "20") (pinfunction "MC+_20") (pintype "bidirectional"))
    )
    (net (code "122") (name "Net-(U4-MC-)") (class "Default")
      (node (ref "C73") (pin "2") (pinfunction "2_2") (pintype "passive"))
      (node (ref "U4") (pin "19") (pinfunction "MC-_19") (pintype "bidirectional"))
    )
    (net (code "123") (name "Net-(U4-MCLK)") (class "Default")
      (node (ref "C67") (pin "2") (pinfunction "2_2") (pintype "passive"))
      (node (ref "R62") (pin "1") (pinfunction "1_1") (pintype "passive"))
      (node (ref "U4") (pin "10") (pinfunction "MCLK_10") (pintype "bidirectional"))
    )
    (net (code "124") (name "Net-(U4-MOUT)") (class "Default")
      (node (ref "C70") (pin "2") (pinfunction "2_2") (pintype "passive"))
      (node (ref "C71") (pin "2") (pinfunction "2_2") (pintype "passive"))
      (node (ref "U4") (pin "13") (pinfunction "MOUT_13") (pintype "bidirectional"))
    )
    (net (code "125") (name "Net-(U4-VDDA)") (class "Default")
      (node (ref "C53") (pin "2") (pinfunction "2_2") (pintype "passive"))
      (node (ref "C54") (pin "2") (pinfunction "2_2") (pintype "passive"))
      (node (ref "C55") (pin "2") (pinfunction "2_2") (pintype "passive"))
      (node (ref "C56") (pin "2") (pinfunction "2_2") (pintype "passive"))
      (node (ref "L2") (pin "2") (pinfunction "2_2") (pintype "passive"))
      (node (ref "U4") (pin "2") (pinfunction "VDDA_2") (pintype "bidirectional"))
    )
    (net (code "126") (name "Net-(U4-VDDD)") (class "Default")
      (node (ref "C57") (pin "2") (pinfunction "2_2") (pintype "passive"))
      (node (ref "C58") (pin "2") (pinfunction "2_2") (pintype "passive"))
      (node (ref "C59") (pin "2") (pinfunction "2_2") (pintype "passive"))
      (node (ref "C60") (pin "2") (pinfunction "2_2") (pintype "passive"))
      (node (ref "L3") (pin "2") (pinfunction "2_2") (pintype "passive"))
      (node (ref "U4") (pin "4") (pinfunction "VDDD_4") (pintype "bidirectional"))
    )
    (net (code "127") (name "Net-(U4-VDDSPK)") (class "Default")
      (node (ref "C61") (pin "2") (pinfunction "2_2") (pintype "passive"))
      (node (ref "C62") (pin "2") (pinfunction "2_2") (pintype "passive"))
      (node (ref "C63") (pin "2") (pinfunction "2_2") (pintype "passive"))
      (node (ref "C64") (pin "2") (pinfunction "2_2") (pintype "passive"))
      (node (ref "L4") (pin "2") (pinfunction "2_2") (pintype "passive"))
      (node (ref "U4") (pin "17") (pinfunction "VDDSPK_17") (pintype "bidirectional"))
    )
    (net (code "128") (name "Net-(U4-VREF)") (class "Default")
      (node (ref "C68") (pin "2") (pinfunction "2_2") (pintype "passive"))
      (node (ref "U4") (pin "18") (pinfunction "VREF_18") (pintype "bidirectional"))
    )
    (net (code "129") (name "Net-(U6-AUX_ANT)") (class "Default")
      (node (ref "C42") (pin "2") (pinfunction "2_2") (pintype "passive"))
      (node (ref "R39") (pin "1") (pinfunction "1_1") (pintype "passive"))
      (node (ref "U6") (pin "59") (pinfunction "AUX_ANT_59") (pintype "bidirectional"))
    )
    (net (code "130") (name "Net-(U6-GNSS_ANT)") (class "Default")
      (node (ref "C45") (pin "2") (pinfunction "2_2") (pintype "passive"))
      (node (ref "U6") (pin "79") (pinfunction "GNSS_ANT_79") (pintype "bidirectional"))
    )
    (net (code "131") (name "Net-(U6-MAIN_ANT)") (class "Default")
      (node (ref "C36") (pin "2") (pinfunction "2_2") (pintype "passive"))
      (node (ref "R34") (pin "1") (pinfunction "1_1") (pintype "passive"))
      (node (ref "U6") (pin "82") (pinfunction "MAIN_ANT_82") (pintype "bidirectional"))
    )
    (net (code "132") (name "Net-(U7-A8)") (class "Default")
      (node (ref "R23") (pin "2") (pinfunction "2_2") (pintype "passive"))
      (node (ref "U7") (pin "9") (pinfunction "A8_9") (pintype "bidirectional"))
    )
    (net (code "133") (name "Net-(USB-LTE-CC1)") (class "Default")
      (node (ref "R26") (pin "1") (pinfunction "1_1") (pintype "passive"))
      (node (ref "USB-LTE") (pin "A5") (pinfunction "CC1_A5") (pintype "bidirectional"))
    )
    (net (code "134") (name "Net-(USB-LTE-CC2)") (class "Default")
      (node (ref "R24") (pin "1") (pinfunction "1_1") (pintype "passive"))
      (node (ref "USB-LTE") (pin "B5") (pinfunction "CC2_B5") (pintype "bidirectional"))
    )
    (net (code "135") (name "Net-(USB-MCU-CC1)") (class "Default")
      (node (ref "R46") (pin "1") (pinfunction "1_1") (pintype "passive"))
      (node (ref "USB-MCU") (pin "A5") (pinfunction "CC1_A5") (pintype "bidirectional"))
    )
    (net (code "136") (name "Net-(USB-MCU-CC2)") (class "Default")
      (node (ref "R48") (pin "1") (pinfunction "1_1") (pintype "passive"))
      (node (ref "USB-MCU") (pin "B5") (pinfunction "CC2_B5") (pintype "bidirectional"))
    )
    (net (code "137") (name "RESET") (class "Default")
      (node (ref "C19") (pin "2") (pinfunction "2_2") (pintype "passive"))
      (node (ref "CN2") (pin "10") (pinfunction "10_10") (pintype "passive"))
      (node (ref "IC2") (pin "40") (pinfunction "RESETN_40") (pintype "bidirectional"))
      (node (ref "J8") (pin "11") (pinfunction "11_11") (pintype "bidirectional"))
      (node (ref "R1") (pin "1") (pinfunction "1_1") (pintype "passive"))
      (node (ref "RESET") (pin "P$1") (pinfunction "1_P$1") (pintype "bidirectional"))
    )
    (net (code "138") (name "VBAT+") (class "Default")
      (node (ref "BAT") (pin "2") (pinfunction "2_2") (pintype "bidirectional"))
      (node (ref "C22") (pin "1") (pinfunction "1_1") (pintype "passive"))
      (node (ref "J2") (pin "11") (pinfunction "11_11") (pintype "bidirectional"))
      (node (ref "J4") (pin "1") (pinfunction "1_1") (pintype "passive"))
      (node (ref "R21") (pin "1") (pinfunction "1_1") (pintype "passive"))
      (node (ref "SW1") (pin "COM1") (pinfunction "COM1_COM1") (pintype "bidirectional"))
      (node (ref "U2") (pin "5") (pinfunction "BAT_5") (pintype "bidirectional"))
    )
    (net (code "139") (name "VBUS") (class "Default")
      (node (ref "C23") (pin "1") (pinfunction "1_1") (pintype "passive"))
      (node (ref "CHG") (pin "2") (pinfunction "2_2") (pintype "bidirectional"))
      (node (ref "D2") (pin "C") (pinfunction "C_C") (pintype "passive"))
      (node (ref "SW1") (pin "COM2") (pinfunction "COM2_COM2") (pintype "bidirectional"))
      (node (ref "U2") (pin "4") (pinfunction "VIN_4") (pintype "bidirectional"))
      (node (ref "U2") (pin "8") (pinfunction "CE_8") (pintype "bidirectional"))
      (node (ref "USB-MCU") (pin "VBUS1") (pinfunction "VBUS_VBUS1") (pintype "bidirectional"))
      (node (ref "USB-MCU") (pin "VBUS2") (pinfunction "VBUS_VBUS2") (pintype "bidirectional"))
    )
    (net (code "140") (name "V_BATT") (class "Default")
      (node (ref "C12") (pin "2") (pinfunction "2_2") (pintype "passive"))
      (node (ref "C46") (pin "2") (pinfunction "2_2") (pintype "passive"))
      (node (ref "C47") (pin "2") (pinfunction "2_2") (pintype "passive"))
      (node (ref "C48") (pin "A") (pinfunction "+_A") (pintype "passive"))
      (node (ref "C8") (pin "2") (pinfunction "2_2") (pintype "passive"))
      (node (ref "D8") (pin "C") (pinfunction "C_C") (pintype "passive"))
      (node (ref "L4") (pin "1") (pinfunction "1_1") (pintype "passive"))
      (node (ref "R18") (pin "2") (pinfunction "2_2") (pintype "passive"))
      (node (ref "R19") (pin "1") (pinfunction "1_1") (pintype "passive"))
      (node (ref "R45") (pin "1") (pinfunction "1_1") (pintype "passive"))
      (node (ref "R6") (pin "2") (pinfunction "2_2") (pintype "passive"))
      (node (ref "R60") (pin "2") (pinfunction "2_2") (pintype "passive"))
      (node (ref "U6") (pin "38") (pinfunction "VBAT1_38") (pintype "bidirectional"))
      (node (ref "U6") (pin "39") (pinfunction "VBAT2_39") (pintype "bidirectional"))
      (node (ref "U6") (pin "62") (pinfunction "VBAT3_62") (pintype "bidirectional"))
      (node (ref "U6") (pin "63") (pinfunction "VBAT4_63") (pintype "bidirectional"))
    )
    (net (code "141") (name "unconnected-(CHG-Pad4)") (class "Default")
      (node (ref "CHG") (pin "4") (pinfunction "4_4") (pintype "bidirectional"))
    )
    (net (code "142") (name "unconnected-(CN2-Pad6)") (class "Default")
      (node (ref "CN2") (pin "6") (pinfunction "6_6") (pintype "passive"))
    )
    (net (code "143") (name "unconnected-(CN2-Pad7)") (class "Default")
      (node (ref "CN2") (pin "7") (pinfunction "7_7") (pintype "passive"))
    )
    (net (code "144") (name "unconnected-(CN2-Pad8)") (class "Default")
      (node (ref "CN2") (pin "8") (pinfunction "8_8") (pintype "passive"))
    )
    (net (code "145") (name "unconnected-(D10-C1-Pad1)") (class "Default")
      (node (ref "D10") (pin "1") (pinfunction "C1_1") (pintype "passive"))
    )
    (net (code "146") (name "unconnected-(EAR-Pad5)") (class "Default")
      (node (ref "EAR") (pin "5") (pinfunction "5_5") (pintype "bidirectional"))
    )
    (net (code "147") (name "unconnected-(EAR-Pad6)") (class "Default")
      (node (ref "EAR") (pin "6") (pinfunction "6_6") (pintype "bidirectional"))
    )
    (net (code "148") (name "unconnected-(EAR-Pad7)") (class "Default")
      (node (ref "EAR") (pin "7") (pinfunction "7_7") (pintype "bidirectional"))
    )
    (net (code "149") (name "unconnected-(EAR-Pad8)") (class "Default")
      (node (ref "EAR") (pin "8") (pinfunction "8_8") (pintype "bidirectional"))
    )
    (net (code "150") (name "unconnected-(IC2-PA13{slash}I2C{slash}EIC{slash}SCOM2PAD1+{slash}TC2-Pad22)") (class "Default")
      (node (ref "IC2") (pin "22") (pinfunction "PA13/I2C/EIC/SCOM2PAD1+/TC2_22") (pintype "bidirectional"))
    )
    (net (code "151") (name "unconnected-(IC2-PA27{slash}EIC-Pad39)") (class "Default")
      (node (ref "IC2") (pin "39") (pinfunction "PA27/EIC_39") (pintype "bidirectional"))
    )
    (net (code "152") (name "unconnected-(IC2-PA28{slash}EIC-Pad41)") (class "Default")
      (node (ref "IC2") (pin "41") (pinfunction "PA28/EIC_41") (pintype "bidirectional"))
    )
    (net (code "153") (name "unconnected-(IC2-PB3{slash}EIC{slash}AIN11{slash}SCOM5PAD1-Pad48)") (class "Default")
      (node (ref "IC2") (pin "48") (pinfunction "PB3/EIC/AIN11/SCOM5PAD1_48") (pintype "bidirectional"))
    )
    (net (code "154") (name "unconnected-(IC2-PB22{slash}EIC{slash}SCOM5PAD2-Pad37)") (class "Default")
      (node (ref "IC2") (pin "37") (pinfunction "PB22/EIC/SCOM5PAD2_37") (pintype "bidirectional"))
    )
    (net (code "155") (name "unconnected-(IC2-PB23{slash}EIC{slash}SCOM5PAD3-Pad38)") (class "Default")
      (node (ref "IC2") (pin "38") (pinfunction "PB23/EIC/SCOM5PAD3_38") (pintype "bidirectional"))
    )
    (net (code "156") (name "unconnected-(SD-MCU-RSV{slash}D1-Pad8)") (class "Default")
      (node (ref "SD-MCU") (pin "8") (pinfunction "RSV/D1_8") (pintype "bidirectional"))
    )
    (net (code "157") (name "unconnected-(SD-MCU-RSV{slash}D2-Pad1)") (class "Default")
      (node (ref "SD-MCU") (pin "1") (pinfunction "RSV/D2_1") (pintype "bidirectional"))
    )
    (net (code "158") (name "unconnected-(SIM-VPP-Pad6)") (class "Default")
      (node (ref "SIM") (pin "6") (pinfunction "VPP_6") (pintype "bidirectional"))
    )
    (net (code "159") (name "unconnected-(SW1-PadCH1B)") (class "Default")
      (node (ref "SW1") (pin "CH1B") (pinfunction "CH1B_CH1B") (pintype "bidirectional"))
    )
    (net (code "160") (name "unconnected-(SW1-PadCH2B)") (class "Default")
      (node (ref "SW1") (pin "CH2B") (pinfunction "CH2B_CH2B") (pintype "bidirectional"))
    )
    (net (code "161") (name "unconnected-(U1-D-Pad4)") (class "Default")
      (node (ref "U1") (pin "4") (pinfunction "D_4") (pintype "bidirectional"))
    )
    (net (code "162") (name "unconnected-(U6-COEX1-Pad83)") (class "Default")
      (node (ref "U6") (pin "83") (pinfunction "COEX1_83") (pintype "bidirectional"))
    )
    (net (code "163") (name "unconnected-(U6-COEX2-Pad84)") (class "Default")
      (node (ref "U6") (pin "84") (pinfunction "COEX2_84") (pintype "bidirectional"))
    )
    (net (code "164") (name "unconnected-(U6-COEX3-Pad86)") (class "Default")
      (node (ref "U6") (pin "86") (pinfunction "COEX3_86") (pintype "bidirectional"))
    )
    (net (code "165") (name "unconnected-(U6-DATA-Pad36)") (class "Default")
      (node (ref "U6") (pin "36") (pinfunction "DATA_36") (pintype "bidirectional"))
    )
    (net (code "166") (name "unconnected-(U6-GPIO3-Pad33)") (class "Default")
      (node (ref "U6") (pin "33") (pinfunction "GPIO3_33") (pintype "bidirectional"))
    )
    (net (code "167") (name "unconnected-(U6-GPIO6-Pad34)") (class "Default")
      (node (ref "U6") (pin "34") (pinfunction "GPIO6_34") (pintype "bidirectional"))
    )
    (net (code "168") (name "unconnected-(U6-GPIO41-Pad52)") (class "Default")
      (node (ref "U6") (pin "52") (pinfunction "GPIO41_52") (pintype "bidirectional"))
    )
    (net (code "169") (name "unconnected-(U6-GPIO43-Pad50)") (class "Default")
      (node (ref "U6") (pin "50") (pinfunction "GPIO43_50") (pintype "bidirectional"))
    )
    (net (code "170") (name "unconnected-(U6-GPIO77-Pad87)") (class "Default")
      (node (ref "U6") (pin "87") (pinfunction "GPIO77_87") (pintype "bidirectional"))
    )
    (net (code "171") (name "unconnected-(U6-NC-Pad42)") (class "Default")
      (node (ref "U6") (pin "42") (pinfunction "NC_42") (pintype "bidirectional"))
    )
    (net (code "172") (name "unconnected-(U6-SDIO_CLK-Pad32)") (class "Default")
      (node (ref "U6") (pin "32") (pinfunction "SDIO_CLK_32") (pintype "bidirectional"))
    )
    (net (code "173") (name "unconnected-(U6-SDIO_CMD-Pad29)") (class "Default")
      (node (ref "U6") (pin "29") (pinfunction "SDIO_CMD_29") (pintype "bidirectional"))
    )
    (net (code "174") (name "unconnected-(U6-SDIO_DATA0-Pad30)") (class "Default")
      (node (ref "U6") (pin "30") (pinfunction "SDIO_DATA0_30") (pintype "bidirectional"))
    )
    (net (code "175") (name "unconnected-(U6-SDIO_DATA1-Pad27)") (class "Default")
      (node (ref "U6") (pin "27") (pinfunction "SDIO_DATA1_27") (pintype "bidirectional"))
    )
    (net (code "176") (name "unconnected-(U6-SDIO_DATA2-Pad28)") (class "Default")
      (node (ref "U6") (pin "28") (pinfunction "SDIO_DATA2_28") (pintype "bidirectional"))
    )
    (net (code "177") (name "unconnected-(U6-SDIO_DATA3-Pad31)") (class "Default")
      (node (ref "U6") (pin "31") (pinfunction "SDIO_DATA3_31") (pintype "bidirectional"))
    )
    (net (code "178") (name "unconnected-(U6-SD_DET-Pad48)") (class "Default")
      (node (ref "U6") (pin "48") (pinfunction "SD_DET_48") (pintype "bidirectional"))
    )
    (net (code "179") (name "unconnected-(U6-SPI_CLK-Pad6)") (class "Default")
      (node (ref "U6") (pin "6") (pinfunction "SPI_CLK_6") (pintype "bidirectional"))
    )
    (net (code "180") (name "unconnected-(U6-SPI_CS-Pad9)") (class "Default")
      (node (ref "U6") (pin "9") (pinfunction "SPI_CS_9") (pintype "bidirectional"))
    )
    (net (code "181") (name "unconnected-(U6-SPI_MISO-Pad7)") (class "Default")
      (node (ref "U6") (pin "7") (pinfunction "SPI_MISO_7") (pintype "bidirectional"))
    )
    (net (code "182") (name "unconnected-(U6-SPI_MOSI-Pad8)") (class "Default")
      (node (ref "U6") (pin "8") (pinfunction "SPI_MOSI_8") (pintype "bidirectional"))
    )
    (net (code "183") (name "unconnected-(U6-STROBE-Pad35)") (class "Default")
      (node (ref "U6") (pin "35") (pinfunction "STROBE_35") (pintype "bidirectional"))
    )
    (net (code "184") (name "unconnected-(U6-USB_ID-Pad16)") (class "Default")
      (node (ref "U6") (pin "16") (pinfunction "USB_ID_16") (pintype "bidirectional"))
    )
    (net (code "185") (name "unconnected-(U6-USIM_DET-Pad53)") (class "Default")
      (node (ref "U6") (pin "53") (pinfunction "USIM_DET_53") (pintype "bidirectional"))
    )
    (net (code "186") (name "unconnected-(U6-VDD_AUX-Pad44)") (class "Default")
      (node (ref "U6") (pin "44") (pinfunction "VDD_AUX_44") (pintype "bidirectional"))
    )
    (net (code "187") (name "unconnected-(U7-B3-Pad17)") (class "Default")
      (node (ref "U7") (pin "17") (pinfunction "B3_17") (pintype "bidirectional"))
    )
    (net (code "188") (name "unconnected-(U7-B4-Pad16)") (class "Default")
      (node (ref "U7") (pin "16") (pinfunction "B4_16") (pintype "bidirectional"))
    )
    (net (code "189") (name "unconnected-(U7-B6-Pad14)") (class "Default")
      (node (ref "U7") (pin "14") (pinfunction "B6_14") (pintype "bidirectional"))
    )
    (net (code "190") (name "unconnected-(U7-B8-Pad12)") (class "Default")
      (node (ref "U7") (pin "12") (pinfunction "B8_12") (pintype "bidirectional"))
    )
    (net (code "191") (name "unconnected-(U8-BYP-Pad4)") (class "Default")
      (node (ref "U8") (pin "4") (pinfunction "BYP_4") (pintype "bidirectional"))
    )
  )
)
